# tarjeta-v7.net
KiCad netlist of a schematic drawn in EAGLE
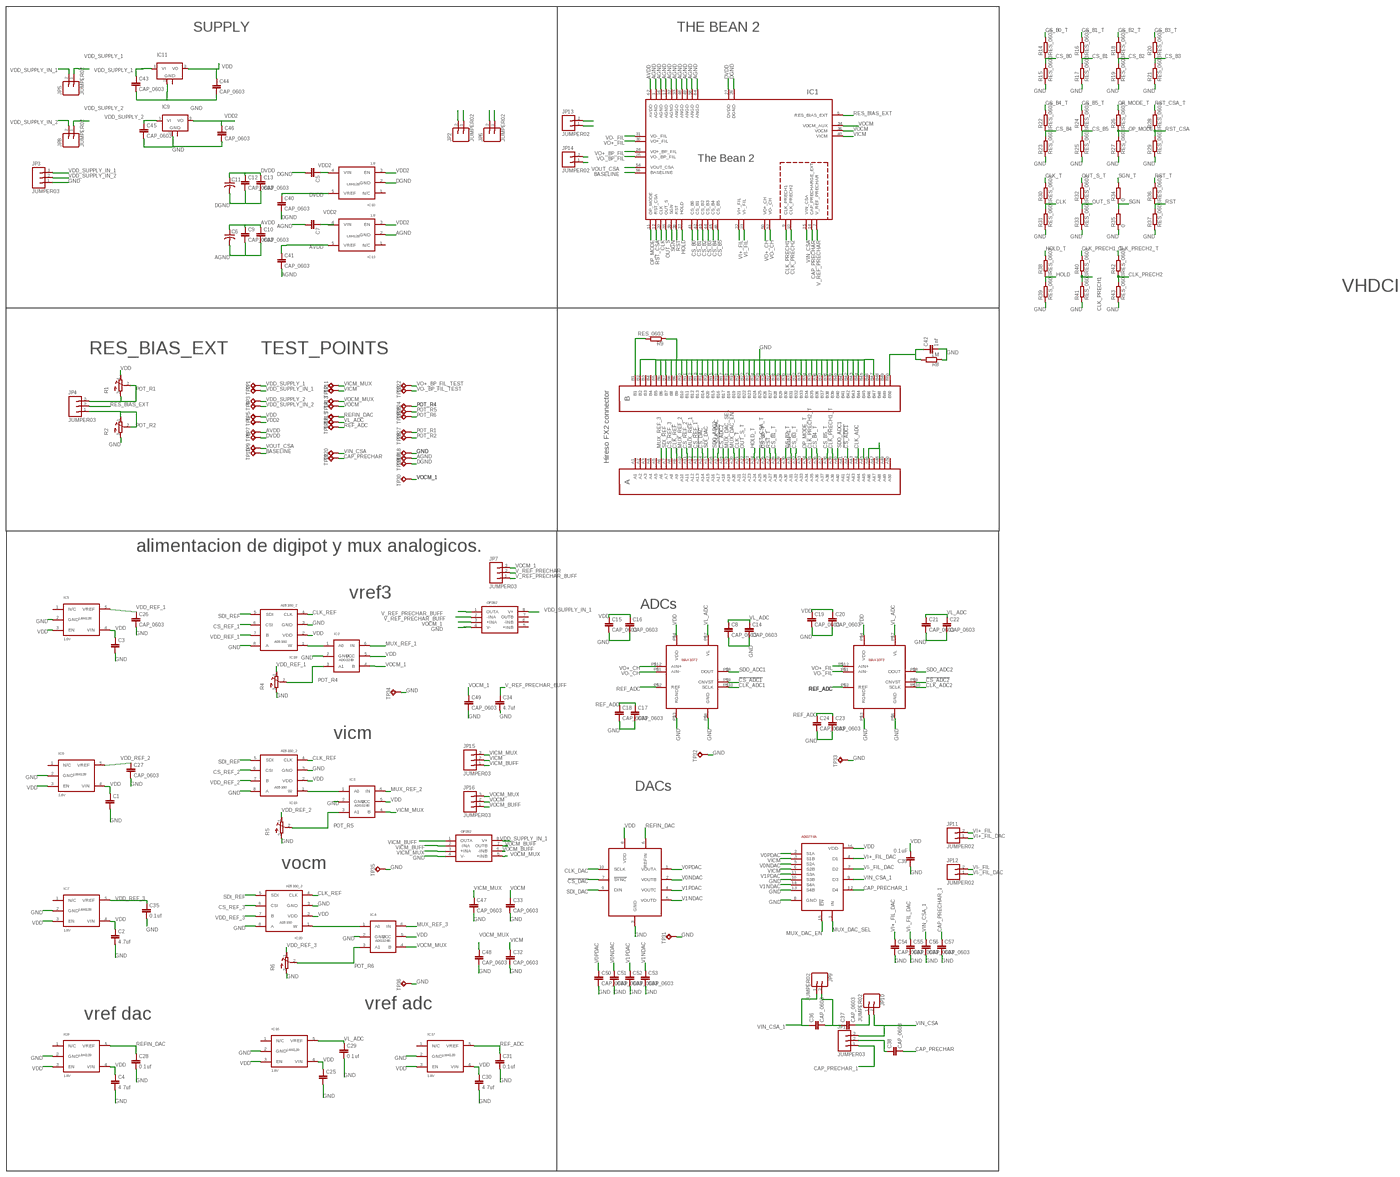
[diagram p0: schematic, sheet 1, overview]
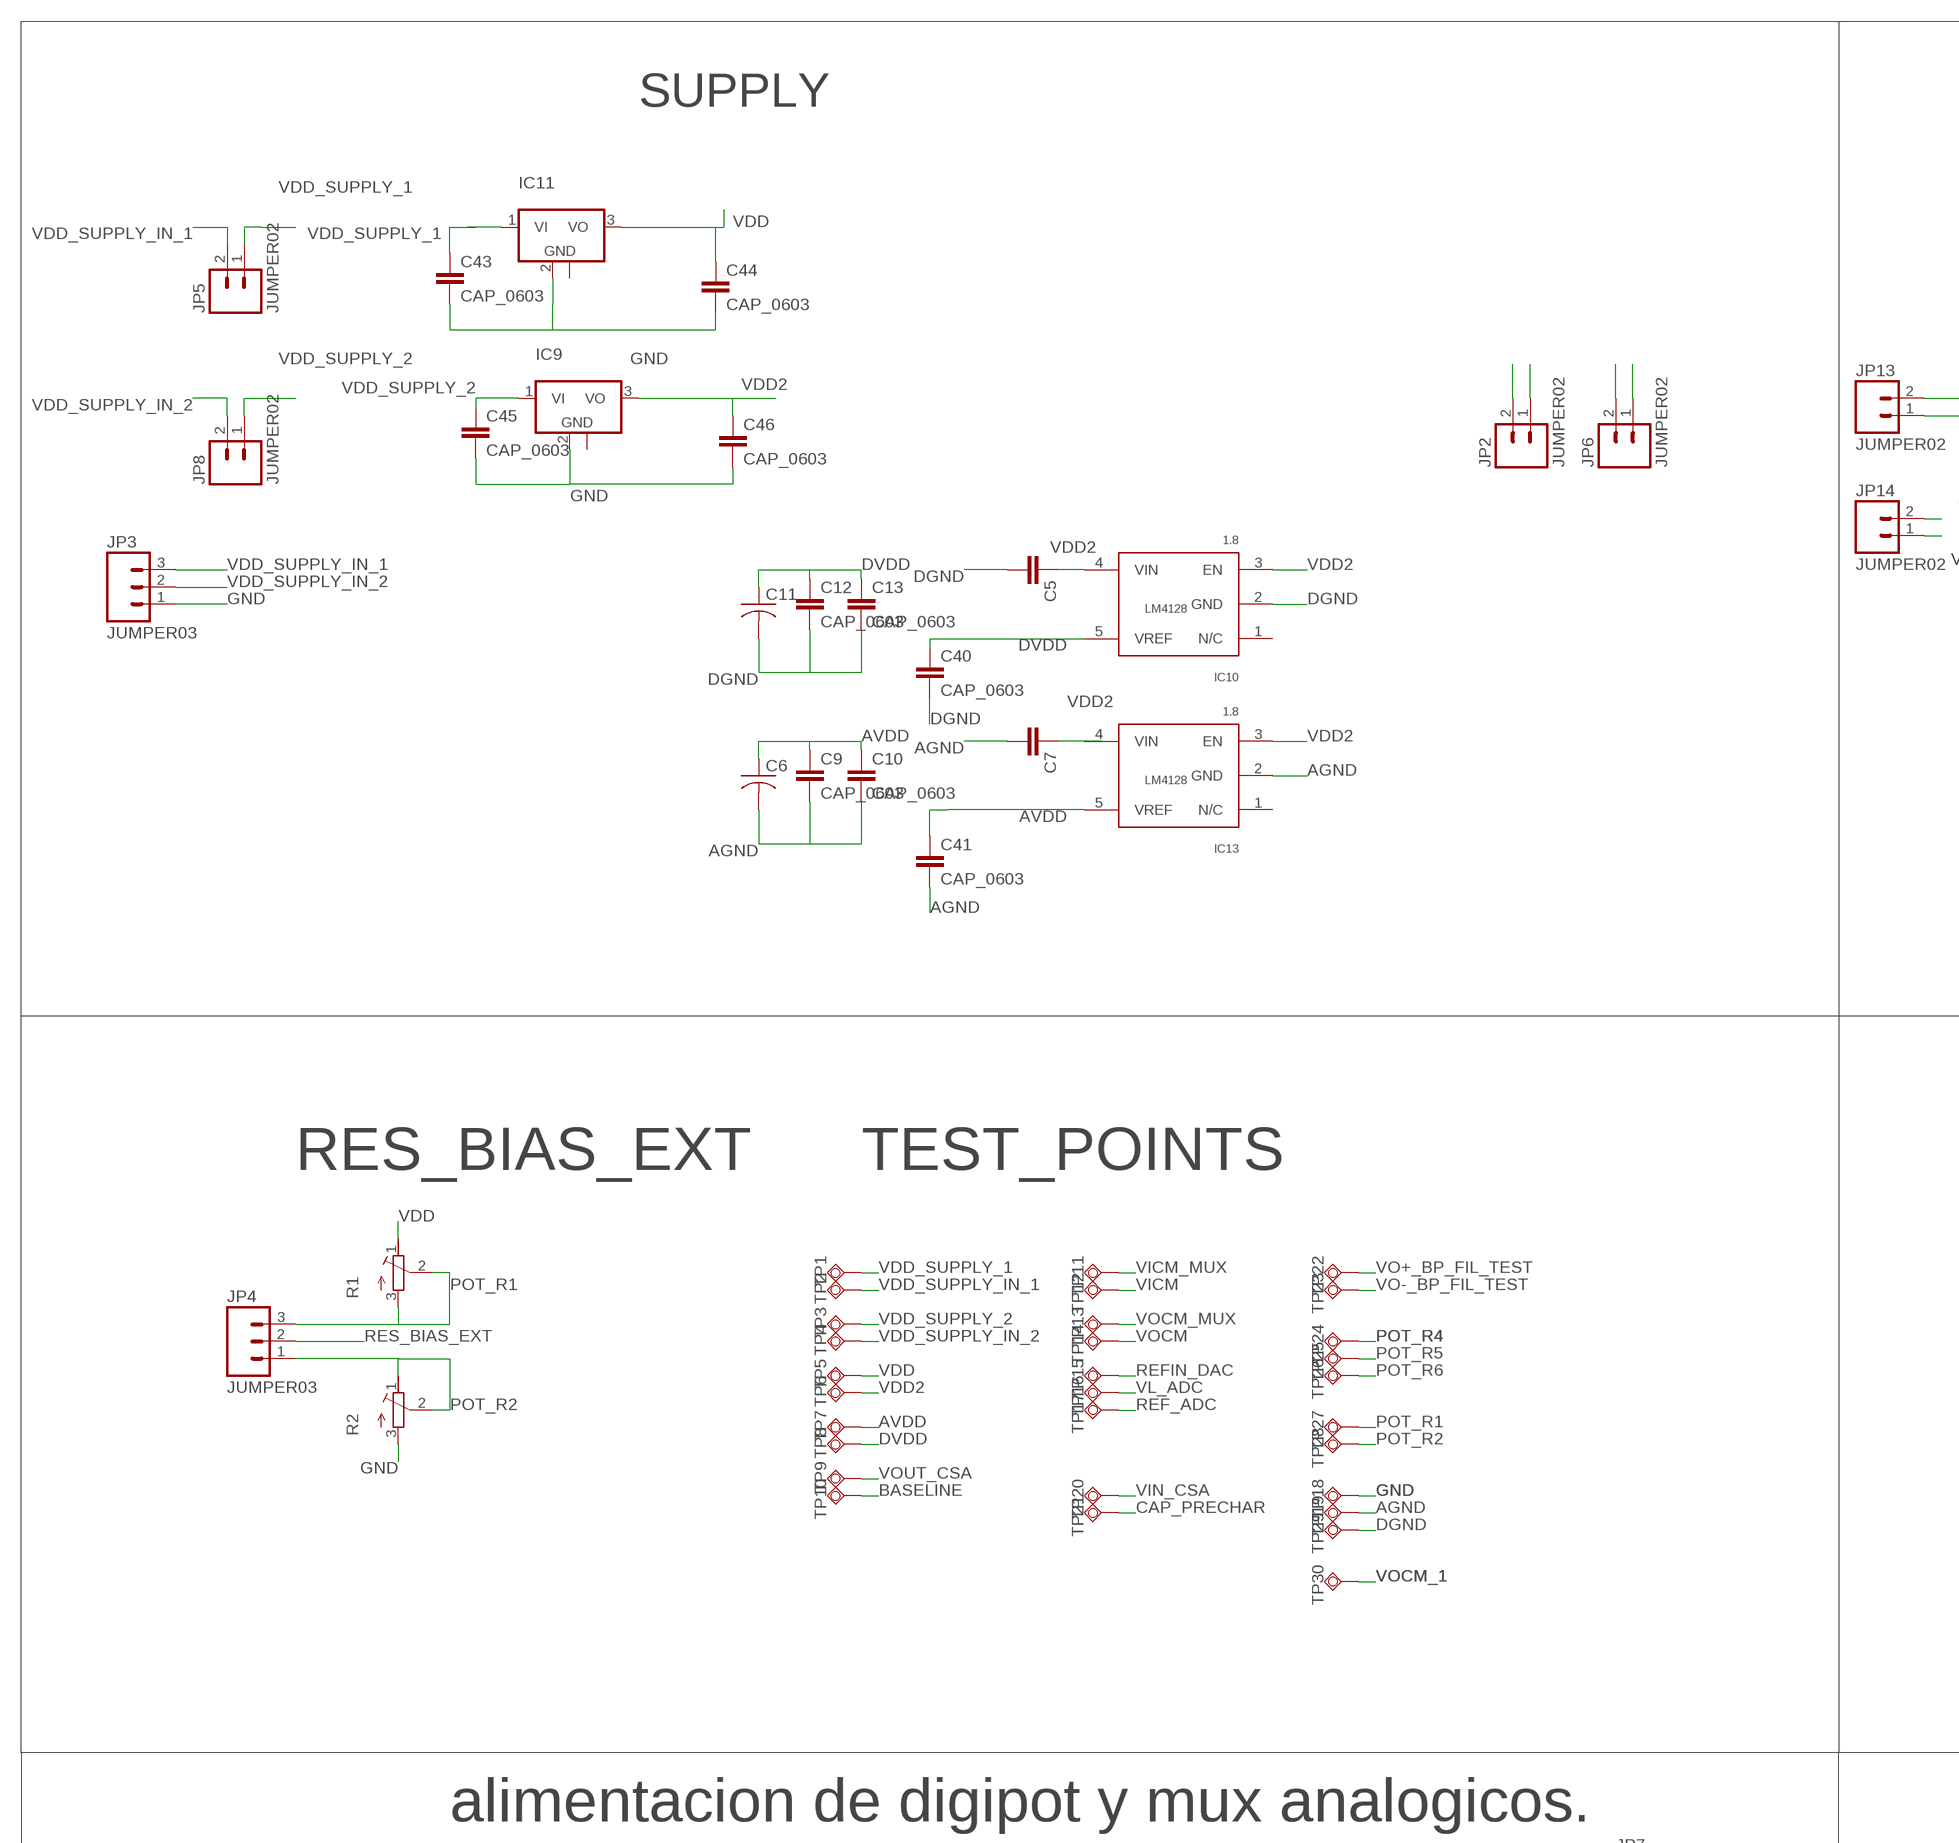
[diagram p1: schematic, sheet 1, part 1 of 4]
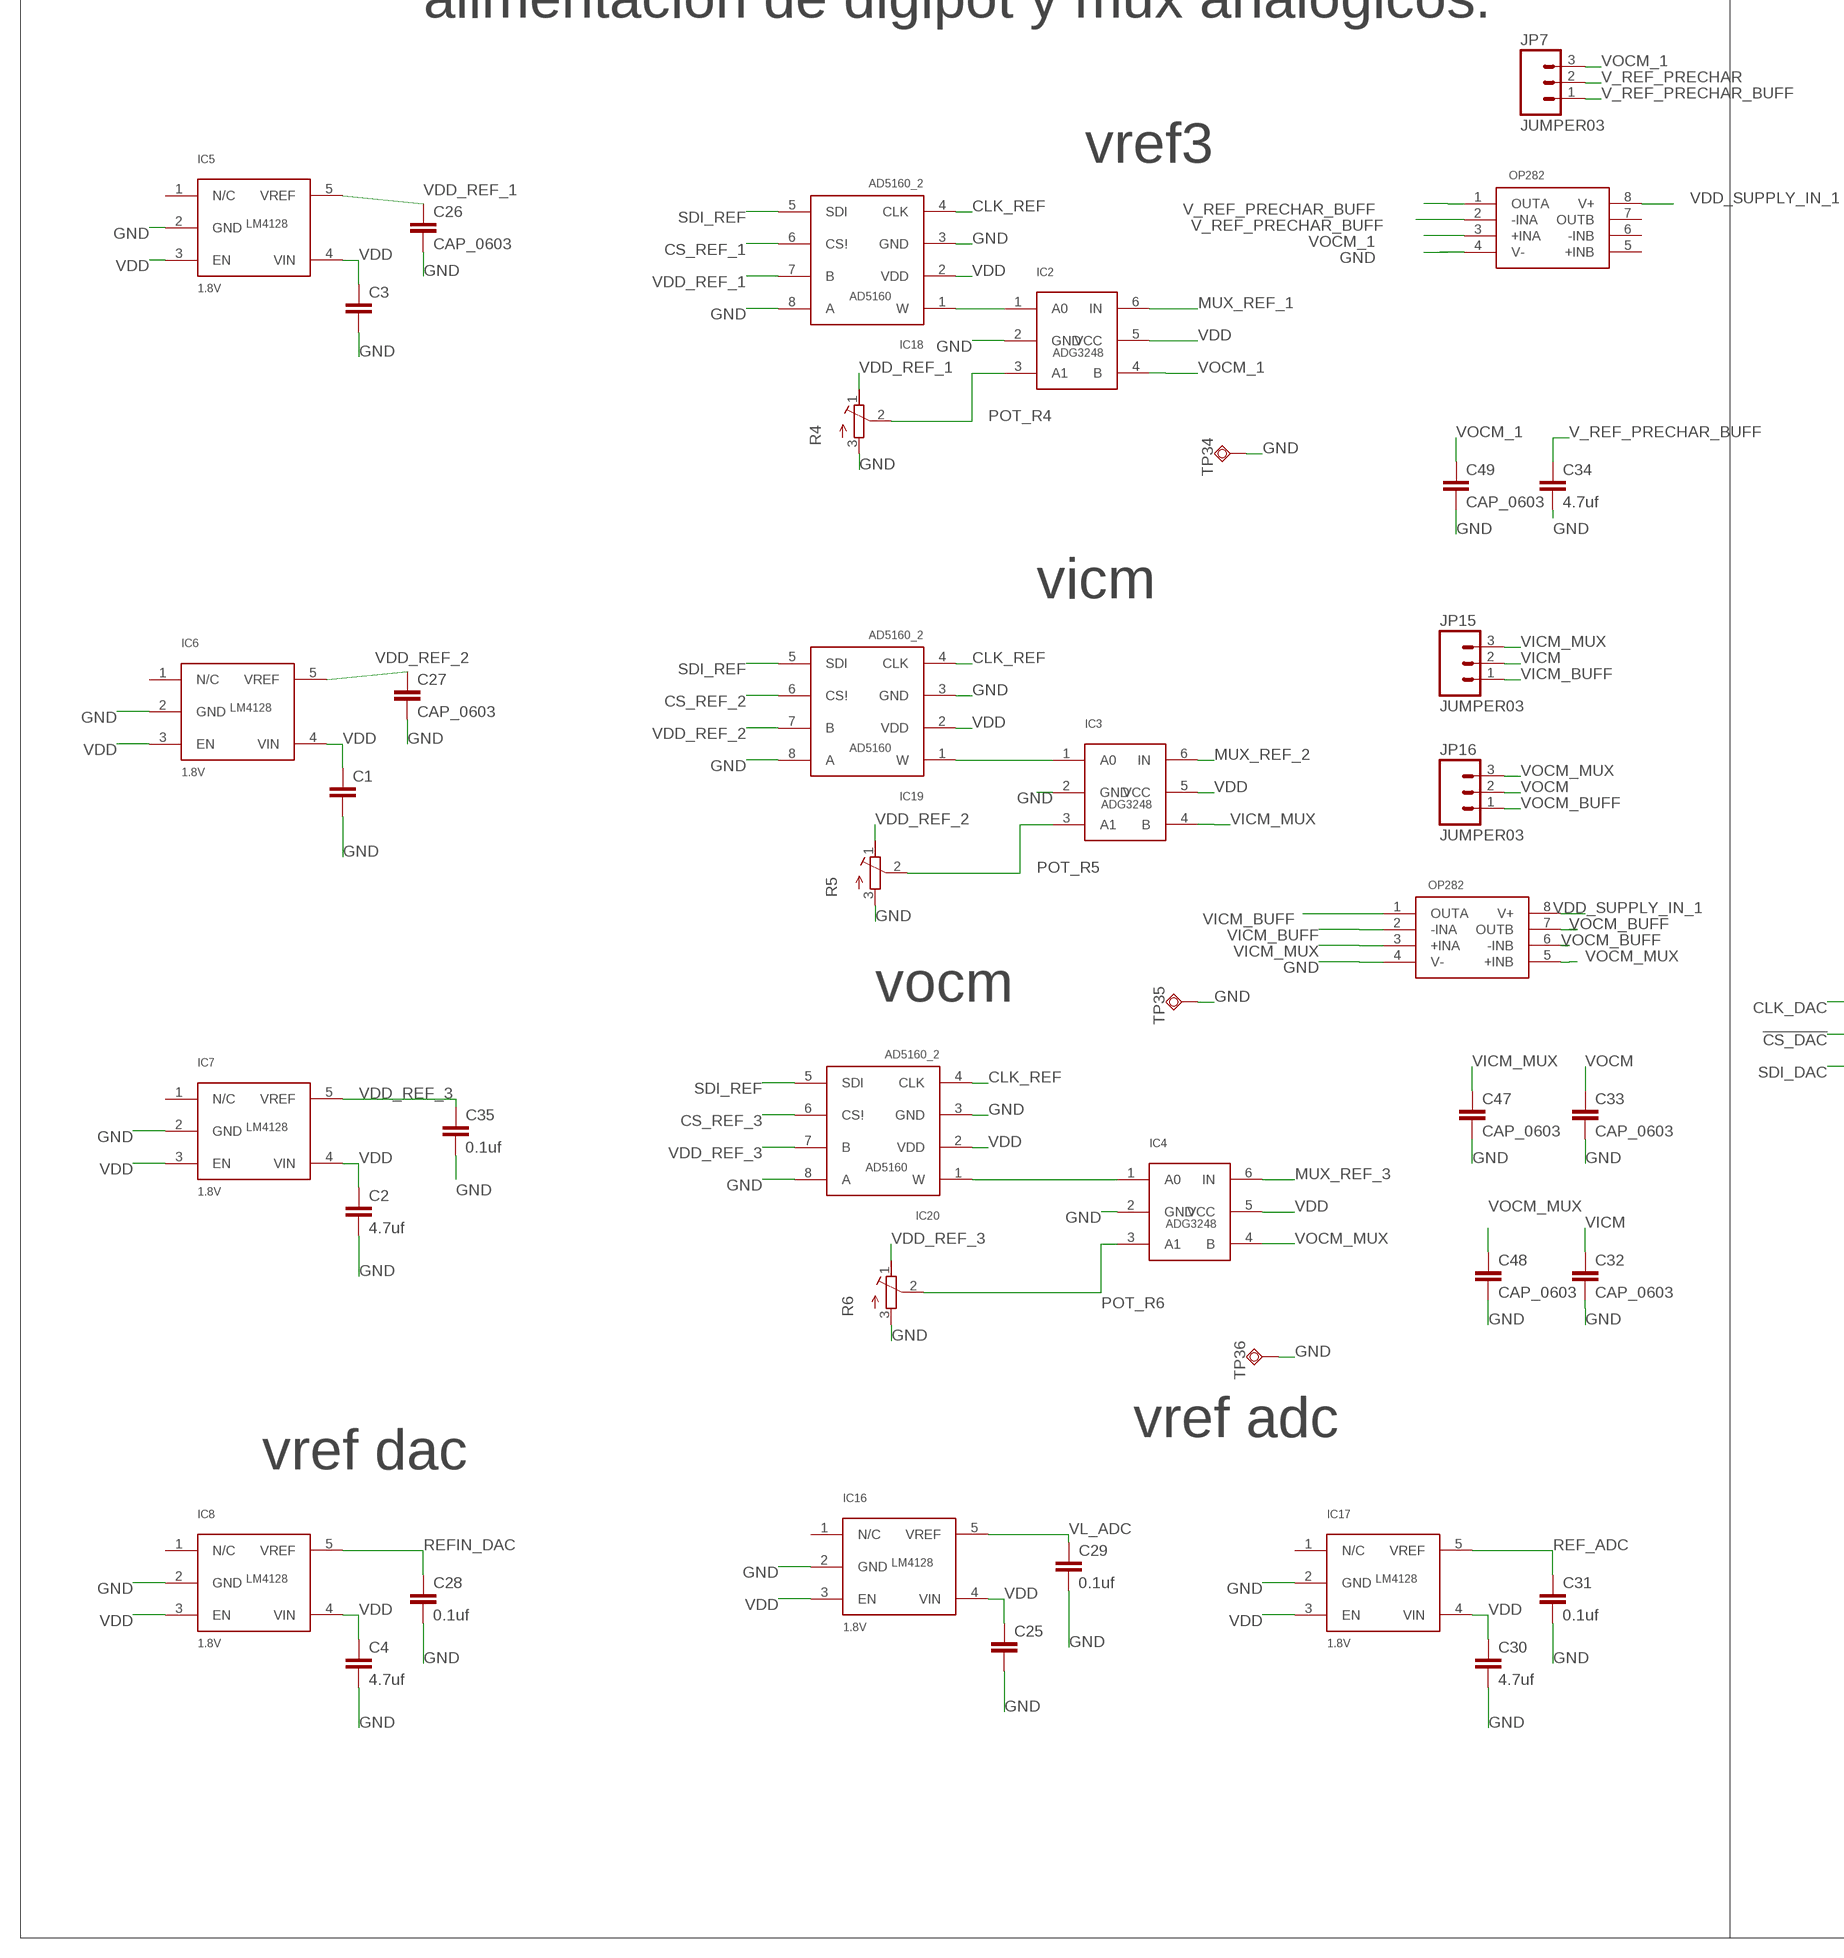
[diagram p2: schematic, sheet 1, part 2 of 4]
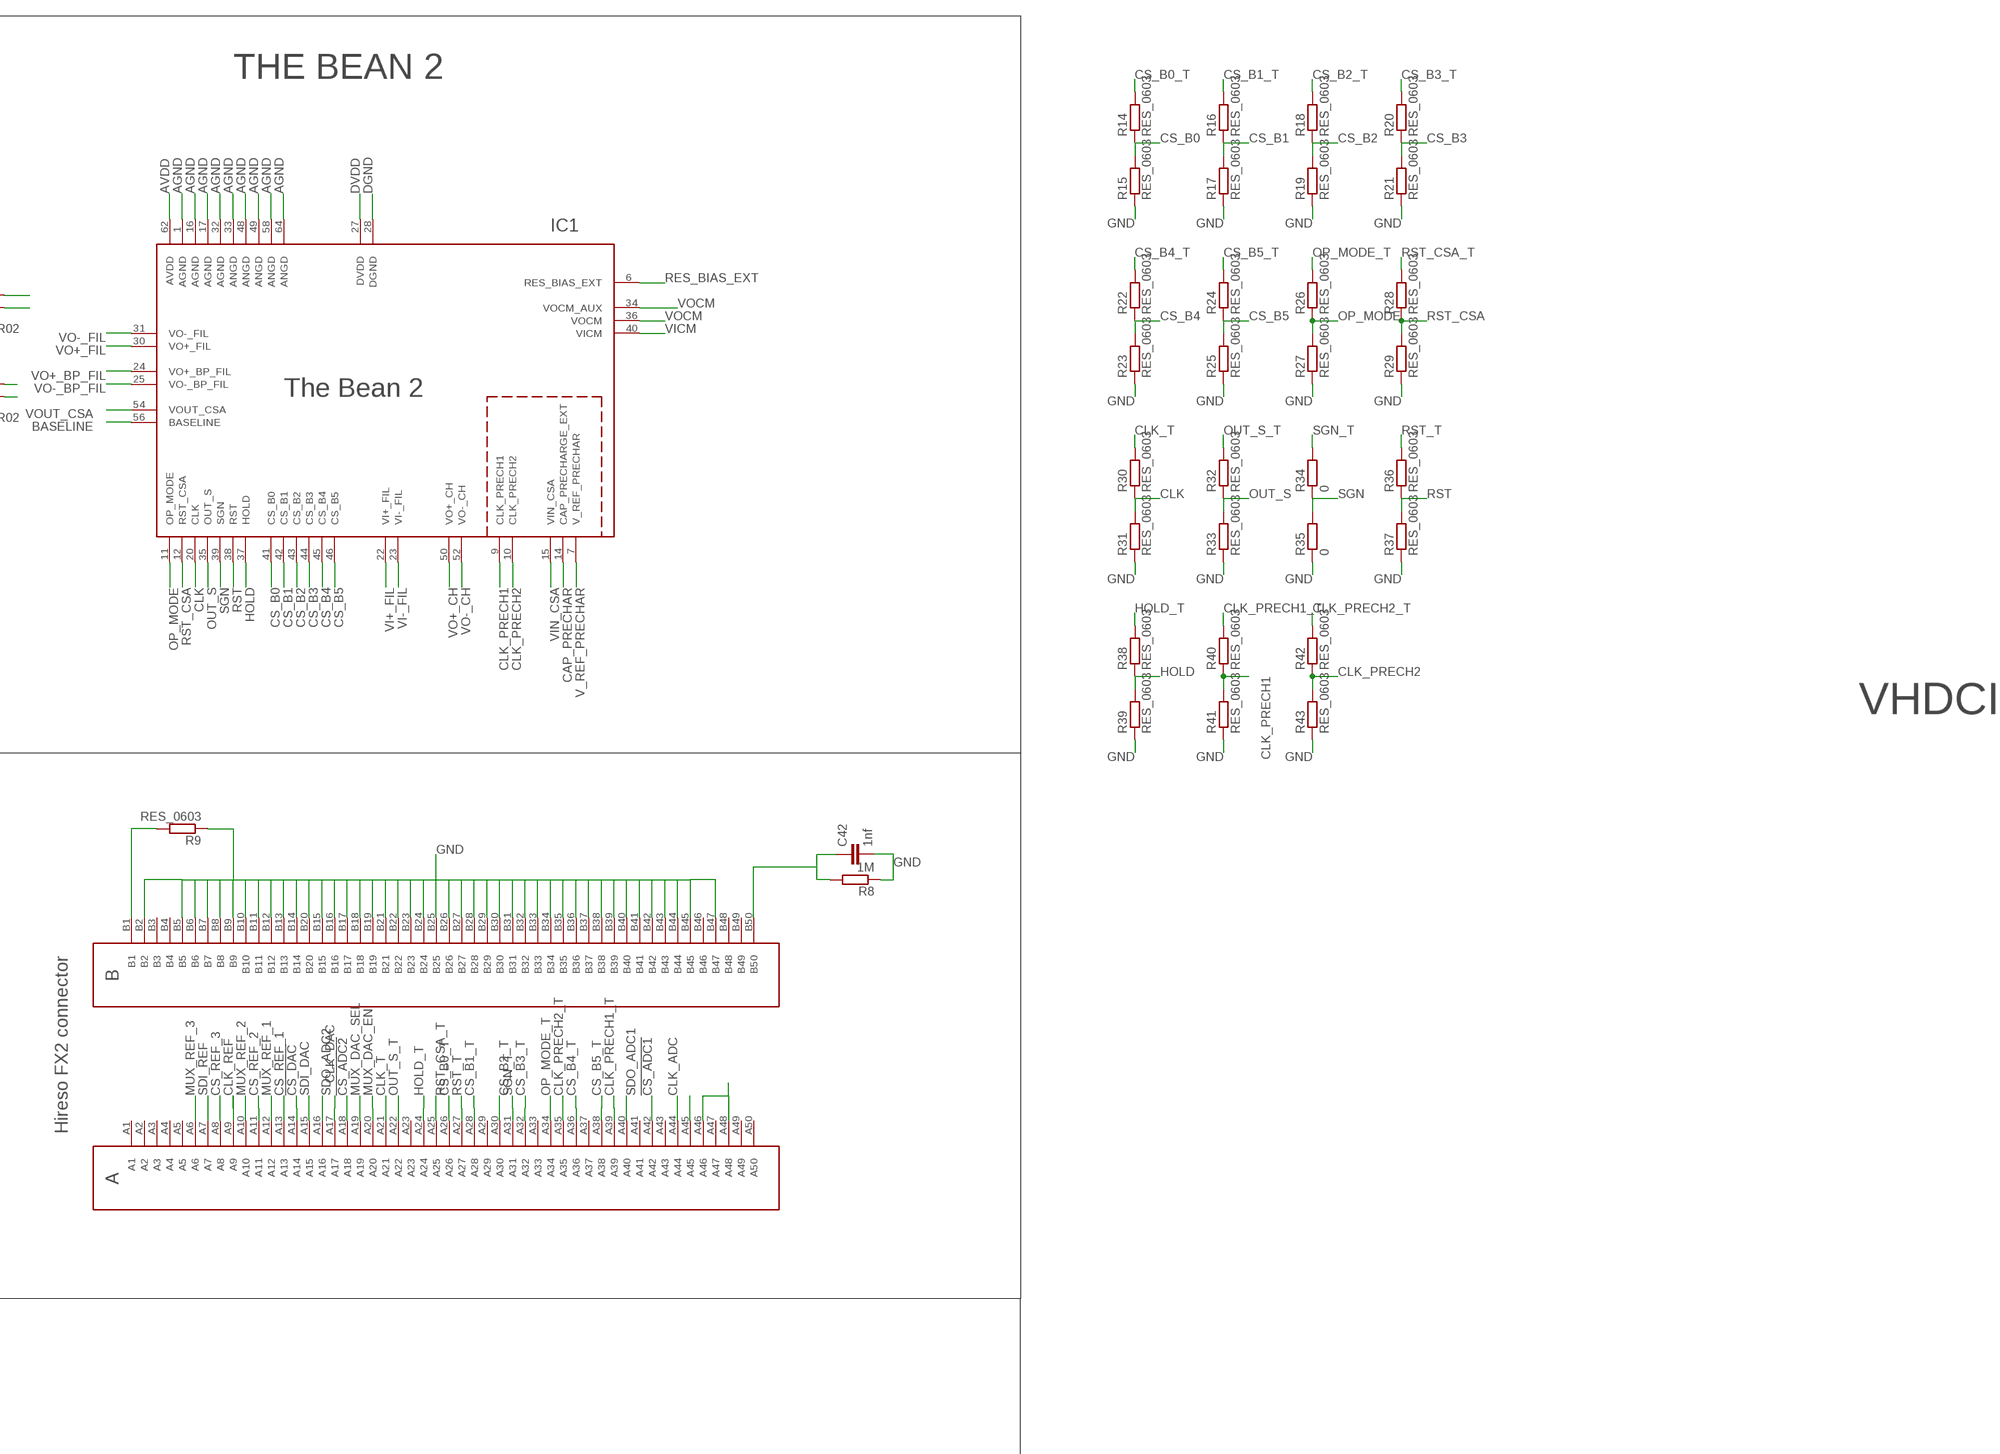
[diagram p3: schematic, sheet 1, part 3 of 4]
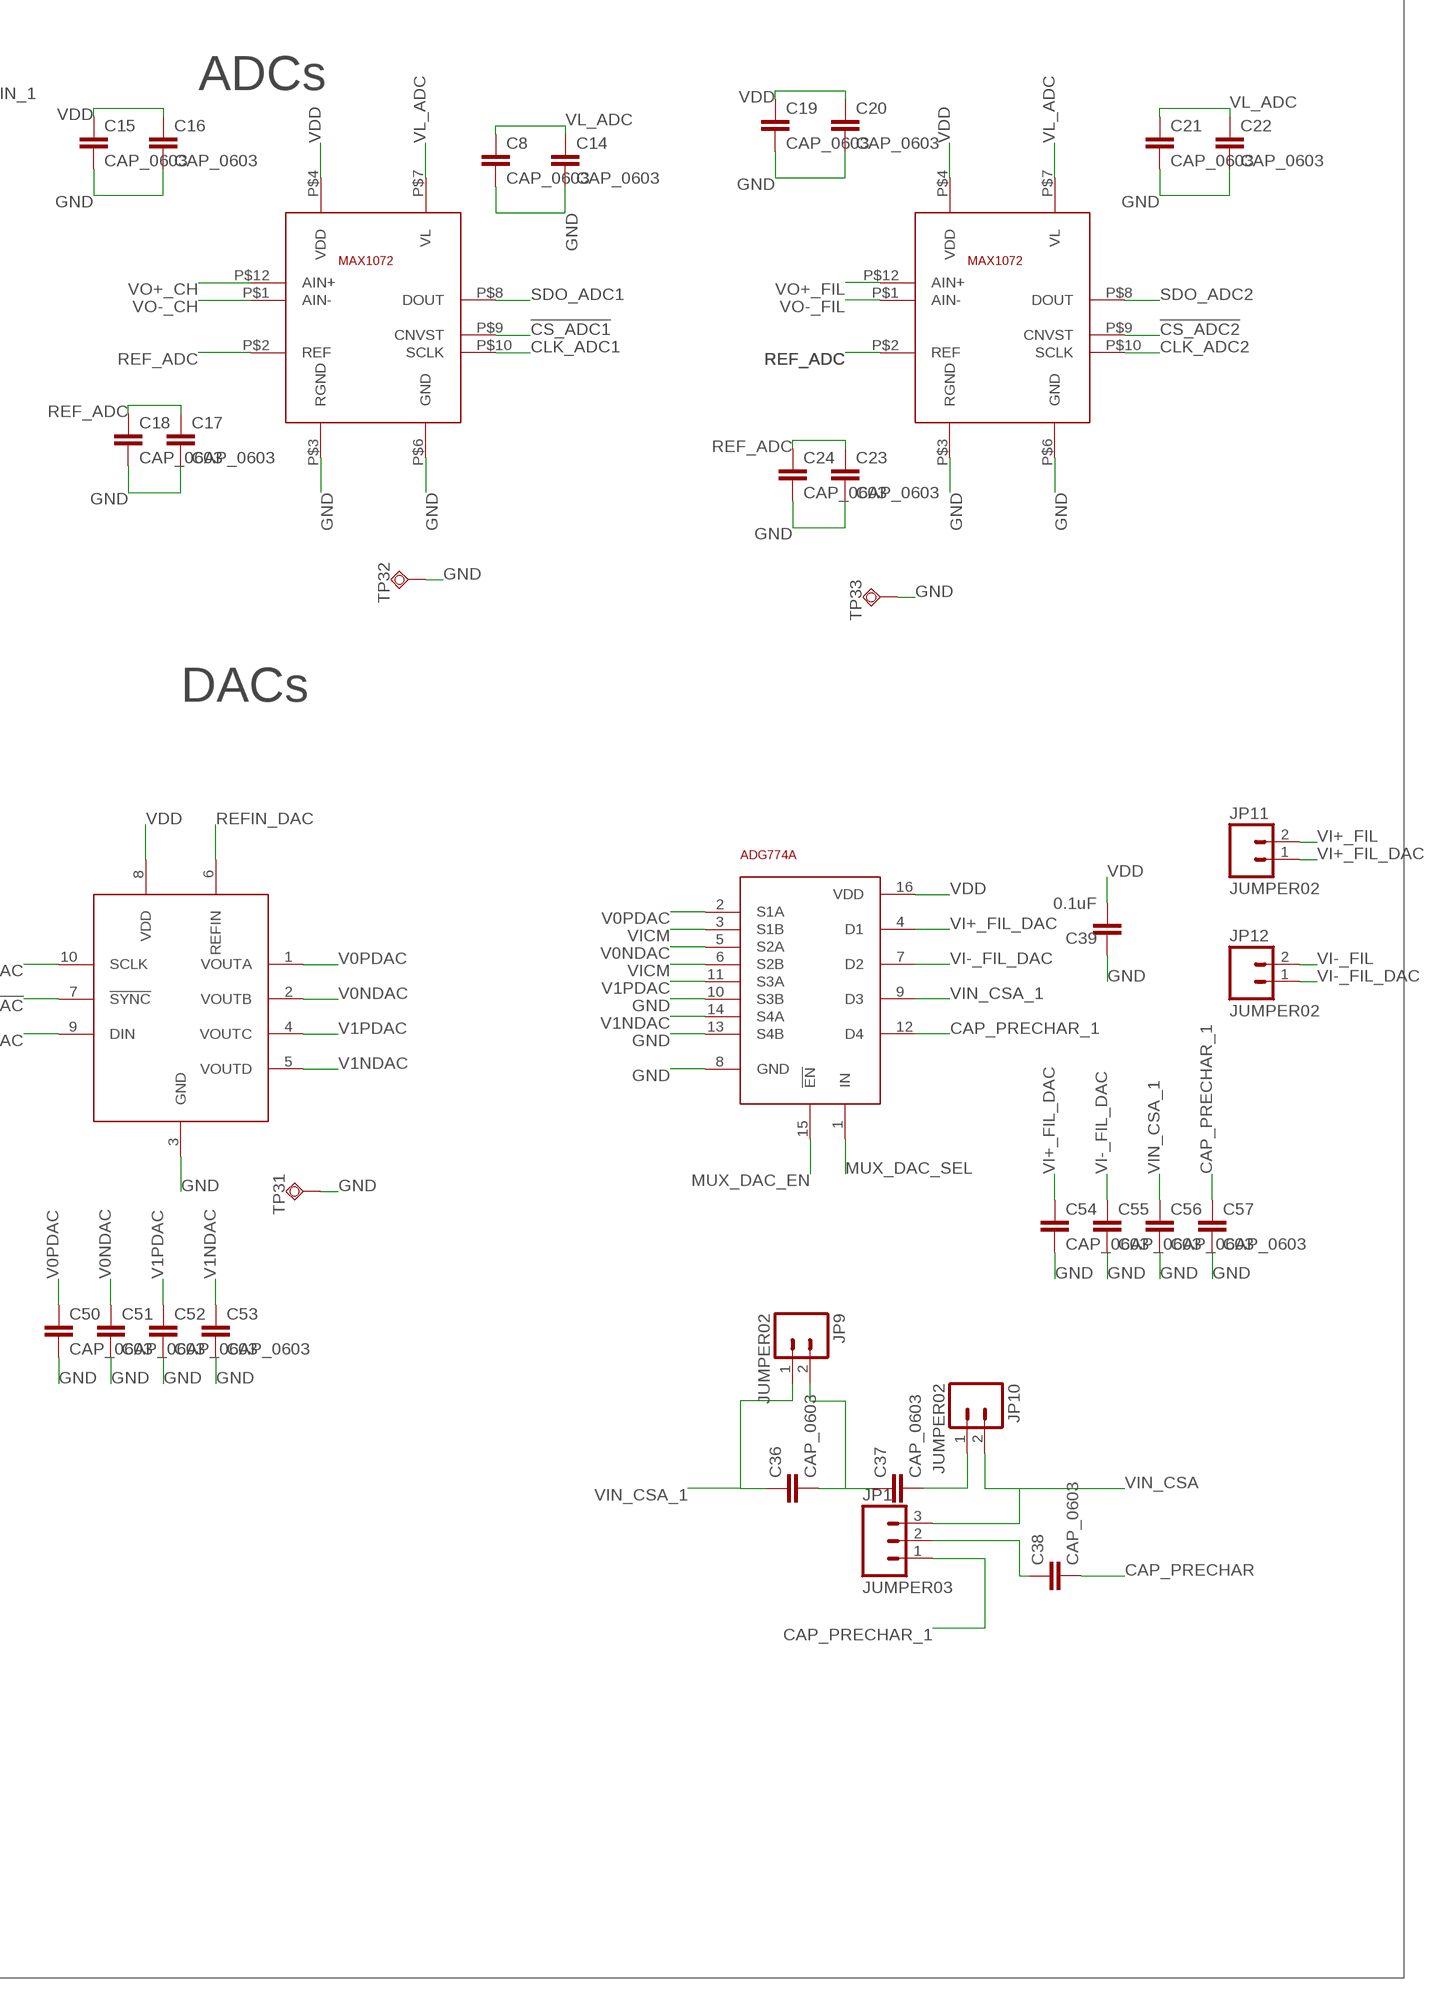
[diagram p4: schematic, sheet 1, part 4 of 4]

(export (version "E")
  (design (tool "Eeschema 10.0.6"))
  (components
    (comp (ref "C1")
      (value "CAP_0402")
      (footprint "eagle-import:C0402")
      (libsource (lib "eagle-import") (part "CAP_0402"))
    )
    (comp (ref "C2")
      (value "4.7uf")
      (footprint "eagle-import:C0402")
      (libsource (lib "eagle-import") (part "CAP_0402"))
    )
    (comp (ref "C3")
      (value "CAP_0402")
      (footprint "eagle-import:C0402")
      (libsource (lib "eagle-import") (part "CAP_0402"))
    )
    (comp (ref "C4")
      (value "4.7uf")
      (footprint "eagle-import:C0402")
      (libsource (lib "eagle-import") (part "CAP_0402"))
    )
    (comp (ref "C5")
      (value "CAP_0402")
      (footprint "eagle-import:C0402")
      (libsource (lib "eagle-import") (part "CAP_0402"))
    )
    (comp (ref "C6")
      (value "CAP_0805")
      (footprint "eagle-import:C0805")
      (libsource (lib "eagle-import") (part "CAP_0805"))
    )
    (comp (ref "C7")
      (value "CAP_0402")
      (footprint "eagle-import:C0402")
      (libsource (lib "eagle-import") (part "CAP_0402"))
    )
    (comp (ref "C8")
      (value "CAP_0603")
      (footprint "eagle-import:C0603")
      (libsource (lib "eagle-import") (part "CAP_0603"))
    )
    (comp (ref "C9")
      (value "CAP_0603")
      (footprint "eagle-import:C0603")
      (libsource (lib "eagle-import") (part "CAP_0603"))
    )
    (comp (ref "C10")
      (value "CAP_0603")
      (footprint "eagle-import:C0603")
      (libsource (lib "eagle-import") (part "CAP_0603"))
    )
    (comp (ref "C11")
      (value "CAP_0805")
      (footprint "eagle-import:C0805")
      (libsource (lib "eagle-import") (part "CAP_0805"))
    )
    (comp (ref "C12")
      (value "CAP_0603")
      (footprint "eagle-import:C0603")
      (libsource (lib "eagle-import") (part "CAP_0603"))
    )
    (comp (ref "C13")
      (value "CAP_0603")
      (footprint "eagle-import:C0603")
      (libsource (lib "eagle-import") (part "CAP_0603"))
    )
    (comp (ref "C14")
      (value "CAP_0603")
      (footprint "eagle-import:C0603")
      (libsource (lib "eagle-import") (part "CAP_0603"))
    )
    (comp (ref "C15")
      (value "CAP_0603")
      (footprint "eagle-import:C0603")
      (libsource (lib "eagle-import") (part "CAP_0603"))
    )
    (comp (ref "C16")
      (value "CAP_0603")
      (footprint "eagle-import:C0603")
      (libsource (lib "eagle-import") (part "CAP_0603"))
    )
    (comp (ref "C17")
      (value "CAP_0603")
      (footprint "eagle-import:C0603")
      (libsource (lib "eagle-import") (part "CAP_0603"))
    )
    (comp (ref "C18")
      (value "CAP_0603")
      (footprint "eagle-import:C0603")
      (libsource (lib "eagle-import") (part "CAP_0603"))
    )
    (comp (ref "C19")
      (value "CAP_0603")
      (footprint "eagle-import:C0603")
      (libsource (lib "eagle-import") (part "CAP_0603"))
    )
    (comp (ref "C20")
      (value "CAP_0603")
      (footprint "eagle-import:C0603")
      (libsource (lib "eagle-import") (part "CAP_0603"))
    )
    (comp (ref "C21")
      (value "CAP_0603")
      (footprint "eagle-import:C0603")
      (libsource (lib "eagle-import") (part "CAP_0603"))
    )
    (comp (ref "C22")
      (value "CAP_0603")
      (footprint "eagle-import:C0603")
      (libsource (lib "eagle-import") (part "CAP_0603"))
    )
    (comp (ref "C23")
      (value "CAP_0603")
      (footprint "eagle-import:C0603")
      (libsource (lib "eagle-import") (part "CAP_0603"))
    )
    (comp (ref "C24")
      (value "CAP_0603")
      (footprint "eagle-import:C0603")
      (libsource (lib "eagle-import") (part "CAP_0603"))
    )
    (comp (ref "C25")
      (value "CAP_0402")
      (footprint "eagle-import:C0402")
      (libsource (lib "eagle-import") (part "CAP_0402"))
    )
    (comp (ref "C26")
      (value "CAP_0603")
      (footprint "eagle-import:C0603")
      (libsource (lib "eagle-import") (part "CAP_0603"))
    )
    (comp (ref "C27")
      (value "CAP_0603")
      (footprint "eagle-import:C0603")
      (libsource (lib "eagle-import") (part "CAP_0603"))
    )
    (comp (ref "C28")
      (value "0.1uf")
      (footprint "eagle-import:C0603")
      (libsource (lib "eagle-import") (part "CAP_0603"))
    )
    (comp (ref "C29")
      (value "0.1uf")
      (footprint "eagle-import:C0603")
      (libsource (lib "eagle-import") (part "CAP_0603"))
    )
    (comp (ref "C30")
      (value "4.7uf")
      (footprint "eagle-import:C0402")
      (libsource (lib "eagle-import") (part "CAP_0402"))
    )
    (comp (ref "C31")
      (value "0.1uf")
      (footprint "eagle-import:C0603")
      (libsource (lib "eagle-import") (part "CAP_0603"))
    )
    (comp (ref "C32")
      (value "CAP_0603")
      (footprint "eagle-import:C0603")
      (libsource (lib "eagle-import") (part "CAP_0603"))
    )
    (comp (ref "C33")
      (value "CAP_0603")
      (footprint "eagle-import:C0603")
      (libsource (lib "eagle-import") (part "CAP_0603"))
    )
    (comp (ref "C34")
      (value "4.7uf")
      (footprint "eagle-import:C0603")
      (libsource (lib "eagle-import") (part "CAP_0603"))
    )
    (comp (ref "C35")
      (value "0.1uf")
      (footprint "eagle-import:C0603")
      (libsource (lib "eagle-import") (part "CAP_0603"))
    )
    (comp (ref "C36")
      (value "CAP_0603")
      (footprint "eagle-import:C0603")
      (libsource (lib "eagle-import") (part "CAP_0603"))
    )
    (comp (ref "C37")
      (value "CAP_0603")
      (footprint "eagle-import:C0603")
      (libsource (lib "eagle-import") (part "CAP_0603"))
    )
    (comp (ref "C38")
      (value "CAP_0603")
      (footprint "eagle-import:C0603")
      (libsource (lib "eagle-import") (part "CAP_0603"))
    )
    (comp (ref "C39")
      (value "0.1uF")
      (footprint "eagle-import:C0603")
      (libsource (lib "eagle-import") (part "CAP_0603"))
    )
    (comp (ref "C40")
      (value "CAP_0603")
      (footprint "eagle-import:C0603")
      (libsource (lib "eagle-import") (part "CAP_0603"))
    )
    (comp (ref "C41")
      (value "CAP_0603")
      (footprint "eagle-import:C0603")
      (libsource (lib "eagle-import") (part "CAP_0603"))
    )
    (comp (ref "C42")
      (value "1nf")
      (footprint "eagle-import:C0603")
      (libsource (lib "eagle-import") (part "CAP_0603"))
    )
    (comp (ref "C43")
      (value "CAP_0603")
      (footprint "eagle-import:C0603")
      (libsource (lib "eagle-import") (part "CAP_0603"))
    )
    (comp (ref "C44")
      (value "CAP_0603")
      (footprint "eagle-import:C0603")
      (libsource (lib "eagle-import") (part "CAP_0603"))
    )
    (comp (ref "C45")
      (value "CAP_0603")
      (footprint "eagle-import:C0603")
      (libsource (lib "eagle-import") (part "CAP_0603"))
    )
    (comp (ref "C46")
      (value "CAP_0603")
      (footprint "eagle-import:C0603")
      (libsource (lib "eagle-import") (part "CAP_0603"))
    )
    (comp (ref "C47")
      (value "CAP_0603")
      (footprint "eagle-import:C0603")
      (libsource (lib "eagle-import") (part "CAP_0603"))
    )
    (comp (ref "C48")
      (value "CAP_0603")
      (footprint "eagle-import:C0603")
      (libsource (lib "eagle-import") (part "CAP_0603"))
    )
    (comp (ref "C49")
      (value "CAP_0603")
      (footprint "eagle-import:C0603")
      (libsource (lib "eagle-import") (part "CAP_0603"))
    )
    (comp (ref "C50")
      (value "CAP_0603")
      (footprint "eagle-import:C0603")
      (libsource (lib "eagle-import") (part "CAP_0603"))
    )
    (comp (ref "C51")
      (value "CAP_0603")
      (footprint "eagle-import:C0603")
      (libsource (lib "eagle-import") (part "CAP_0603"))
    )
    (comp (ref "C52")
      (value "CAP_0603")
      (footprint "eagle-import:C0603")
      (libsource (lib "eagle-import") (part "CAP_0603"))
    )
    (comp (ref "C53")
      (value "CAP_0603")
      (footprint "eagle-import:C0603")
      (libsource (lib "eagle-import") (part "CAP_0603"))
    )
    (comp (ref "C54")
      (value "CAP_0603")
      (footprint "eagle-import:C0603")
      (libsource (lib "eagle-import") (part "CAP_0603"))
    )
    (comp (ref "C55")
      (value "CAP_0603")
      (footprint "eagle-import:C0603")
      (libsource (lib "eagle-import") (part "CAP_0603"))
    )
    (comp (ref "C56")
      (value "CAP_0603")
      (footprint "eagle-import:C0603")
      (libsource (lib "eagle-import") (part "CAP_0603"))
    )
    (comp (ref "C57")
      (value "CAP_0603")
      (footprint "eagle-import:C0603")
      (libsource (lib "eagle-import") (part "CAP_0603"))
    )
    (comp (ref "IC1")
      (value "THE_BEAN_2")
      (footprint "eagle-import:QFN64")
      (libsource (lib "eagle-import") (part "THE_BEAN_2"))
    )
    (comp (ref "IC2")
      (value "ADG3248")
      (footprint "eagle-import:SC70")
      (libsource (lib "eagle-import") (part "ADG3248"))
    )
    (comp (ref "IC3")
      (value "ADG3248")
      (footprint "eagle-import:SC70")
      (libsource (lib "eagle-import") (part "ADG3248"))
    )
    (comp (ref "IC4")
      (value "ADG3248")
      (footprint "eagle-import:SC70")
      (libsource (lib "eagle-import") (part "ADG3248"))
    )
    (comp (ref "IC5")
      (value "1.8V")
      (footprint "eagle-import:SOT23-5L_2")
      (libsource (lib "eagle-import") (part "LM4128_2"))
    )
    (comp (ref "IC6")
      (value "1.8V")
      (footprint "eagle-import:SOT23-5L_2")
      (libsource (lib "eagle-import") (part "LM4128_2"))
    )
    (comp (ref "IC7")
      (value "1.8V")
      (footprint "eagle-import:SOT23-5L_2")
      (libsource (lib "eagle-import") (part "LM4128_2"))
    )
    (comp (ref "IC8")
      (value "1.8V")
      (footprint "eagle-import:SOT23-5L_2")
      (libsource (lib "eagle-import") (part "LM4128_2"))
    )
    (comp (ref "IC9")
      (value "UA78M33DCY")
      (footprint "eagle-import:SOT223")
      (libsource (lib "eagle-import") (part "UA78MDCY33"))
    )
    (comp (ref "IC10")
      (value "1.8")
      (footprint "eagle-import:SOT23-5L_2")
      (libsource (lib "eagle-import") (part "LM4128_2"))
    )
    (comp (ref "IC11")
      (value "UA78M33DCY")
      (footprint "eagle-import:SOT223")
      (libsource (lib "eagle-import") (part "UA78MDCY33"))
    )
    (comp (ref "IC12")
      (value "OP282")
      (footprint "eagle-import:MSOP8")
      (libsource (lib "eagle-import") (part "OP282"))
    )
    (comp (ref "IC13")
      (value "1.8")
      (footprint "eagle-import:SOT23-5L_2")
      (libsource (lib "eagle-import") (part "LM4128_2"))
    )
    (comp (ref "IC14")
      (value "OP282")
      (footprint "eagle-import:MSOP8")
      (libsource (lib "eagle-import") (part "OP282"))
    )
    (comp (ref "IC16")
      (value "1.8V")
      (footprint "eagle-import:SOT23-5L_2")
      (libsource (lib "eagle-import") (part "LM4128_2"))
    )
    (comp (ref "IC17")
      (value "1.8V")
      (footprint "eagle-import:SOT23-5L_2")
      (libsource (lib "eagle-import") (part "LM4128_2"))
    )
    (comp (ref "IC18")
      (value "AD5160_2")
      (footprint "eagle-import:SOT23-8_2")
      (libsource (lib "eagle-import") (part "AD5160_2"))
    )
    (comp (ref "IC19")
      (value "AD5160_2")
      (footprint "eagle-import:SOT23-8_2")
      (libsource (lib "eagle-import") (part "AD5160_2"))
    )
    (comp (ref "IC20")
      (value "AD5160_2")
      (footprint "eagle-import:SOT23-8_2")
      (libsource (lib "eagle-import") (part "AD5160_2"))
    )
    (comp (ref "IC21")
      (value "ADG774A")
      (footprint "eagle-import:QSOP16")
      (libsource (lib "eagle-import") (part "ADG774A"))
    )
    (comp (ref "IC22")
      (value "MAX1072")
      (footprint "eagle-import:TQFN12")
      (libsource (lib "eagle-import") (part "MAX1072"))
    )
    (comp (ref "IC23")
      (value "DAC7554")
      (footprint "eagle-import:MSOP10")
      (libsource (lib "eagle-import") (part "DAC7554"))
    )
    (comp (ref "J1")
      (value "HIRESO_FX_CONNECTOR")
      (footprint "eagle-import:FX2-100S-1.27")
      (libsource (lib "eagle-import") (part "HIRESO_FX_CONNECTOR"))
    )
    (comp (ref "JP1")
      (value "JUMPER03")
      (footprint "eagle-import:1X03")
      (libsource (lib "eagle-import") (part "JUMPER03"))
    )
    (comp (ref "JP2")
      (value "JUMPER02")
      (footprint "eagle-import:1X02")
      (libsource (lib "eagle-import") (part "JUMPER02"))
    )
    (comp (ref "JP3")
      (value "JUMPER03")
      (footprint "eagle-import:1X03")
      (libsource (lib "eagle-import") (part "JUMPER03"))
    )
    (comp (ref "JP4")
      (value "JUMPER03")
      (footprint "eagle-import:1X03")
      (libsource (lib "eagle-import") (part "JUMPER03"))
    )
    (comp (ref "JP5")
      (value "JUMPER02")
      (footprint "eagle-import:1X02")
      (libsource (lib "eagle-import") (part "JUMPER02"))
    )
    (comp (ref "JP6")
      (value "JUMPER02")
      (footprint "eagle-import:1X02")
      (libsource (lib "eagle-import") (part "JUMPER02"))
    )
    (comp (ref "JP7")
      (value "JUMPER03")
      (footprint "eagle-import:1X03")
      (libsource (lib "eagle-import") (part "JUMPER03"))
    )
    (comp (ref "JP8")
      (value "JUMPER02")
      (footprint "eagle-import:1X02")
      (libsource (lib "eagle-import") (part "JUMPER02"))
    )
    (comp (ref "JP9")
      (value "JUMPER02")
      (footprint "eagle-import:1X02")
      (libsource (lib "eagle-import") (part "JUMPER02"))
    )
    (comp (ref "JP10")
      (value "JUMPER02")
      (footprint "eagle-import:1X02")
      (libsource (lib "eagle-import") (part "JUMPER02"))
    )
    (comp (ref "JP11")
      (value "JUMPER02")
      (footprint "eagle-import:1X02")
      (libsource (lib "eagle-import") (part "JUMPER02"))
    )
    (comp (ref "JP12")
      (value "JUMPER02")
      (footprint "eagle-import:1X02")
      (libsource (lib "eagle-import") (part "JUMPER02"))
    )
    (comp (ref "JP13")
      (value "JUMPER02")
      (footprint "eagle-import:1X02")
      (libsource (lib "eagle-import") (part "JUMPER02"))
    )
    (comp (ref "JP14")
      (value "JUMPER02")
      (footprint "eagle-import:1X02")
      (libsource (lib "eagle-import") (part "JUMPER02"))
    )
    (comp (ref "JP15")
      (value "JUMPER03")
      (footprint "eagle-import:1X03")
      (libsource (lib "eagle-import") (part "JUMPER03"))
    )
    (comp (ref "JP16")
      (value "JUMPER03")
      (footprint "eagle-import:1X03")
      (libsource (lib "eagle-import") (part "JUMPER03"))
    )
    (comp (ref "R1")
      (value "TRIMMER_ST5")
      (footprint "eagle-import:ST-5EW")
      (libsource (lib "eagle-import") (part "TRIMMER_ST5"))
    )
    (comp (ref "R2")
      (value "TRIMMER_ST5")
      (footprint "eagle-import:ST-5EW")
      (libsource (lib "eagle-import") (part "TRIMMER_ST5"))
    )
    (comp (ref "R4")
      (value "TRIMMER_ST5")
      (footprint "eagle-import:ST-5EW")
      (libsource (lib "eagle-import") (part "TRIMMER_ST5"))
    )
    (comp (ref "R5")
      (value "TRIMMER_ST5")
      (footprint "eagle-import:ST-5EW")
      (libsource (lib "eagle-import") (part "TRIMMER_ST5"))
    )
    (comp (ref "R6")
      (value "TRIMMER_ST5")
      (footprint "eagle-import:ST-5EW")
      (libsource (lib "eagle-import") (part "TRIMMER_ST5"))
    )
    (comp (ref "R8")
      (value "1M")
      (footprint "eagle-import:R0603")
      (libsource (lib "eagle-import") (part "RES_0603"))
    )
    (comp (ref "R9")
      (value "RES_0603")
      (footprint "eagle-import:R0603")
      (libsource (lib "eagle-import") (part "RES_0603"))
    )
    (comp (ref "R14")
      (value "RES_0603")
      (footprint "eagle-import:R0603")
      (libsource (lib "eagle-import") (part "RES_0603"))
    )
    (comp (ref "R15")
      (value "RES_0603")
      (footprint "eagle-import:R0603")
      (libsource (lib "eagle-import") (part "RES_0603"))
    )
    (comp (ref "R16")
      (value "RES_0603")
      (footprint "eagle-import:R0603")
      (libsource (lib "eagle-import") (part "RES_0603"))
    )
    (comp (ref "R17")
      (value "RES_0603")
      (footprint "eagle-import:R0603")
      (libsource (lib "eagle-import") (part "RES_0603"))
    )
    (comp (ref "R18")
      (value "RES_0603")
      (footprint "eagle-import:R0603")
      (libsource (lib "eagle-import") (part "RES_0603"))
    )
    (comp (ref "R19")
      (value "RES_0603")
      (footprint "eagle-import:R0603")
      (libsource (lib "eagle-import") (part "RES_0603"))
    )
    (comp (ref "R20")
      (value "RES_0603")
      (footprint "eagle-import:R0603")
      (libsource (lib "eagle-import") (part "RES_0603"))
    )
    (comp (ref "R21")
      (value "RES_0603")
      (footprint "eagle-import:R0603")
      (libsource (lib "eagle-import") (part "RES_0603"))
    )
    (comp (ref "R22")
      (value "RES_0603")
      (footprint "eagle-import:R0603")
      (libsource (lib "eagle-import") (part "RES_0603"))
    )
    (comp (ref "R23")
      (value "RES_0603")
      (footprint "eagle-import:R0603")
      (libsource (lib "eagle-import") (part "RES_0603"))
    )
    (comp (ref "R24")
      (value "RES_0603")
      (footprint "eagle-import:R0603")
      (libsource (lib "eagle-import") (part "RES_0603"))
    )
    (comp (ref "R25")
      (value "RES_0603")
      (footprint "eagle-import:R0603")
      (libsource (lib "eagle-import") (part "RES_0603"))
    )
    (comp (ref "R26")
      (value "RES_0603")
      (footprint "eagle-import:R0603")
      (libsource (lib "eagle-import") (part "RES_0603"))
    )
    (comp (ref "R27")
      (value "RES_0603")
      (footprint "eagle-import:R0603")
      (libsource (lib "eagle-import") (part "RES_0603"))
    )
    (comp (ref "R28")
      (value "RES_0603")
      (footprint "eagle-import:R0603")
      (libsource (lib "eagle-import") (part "RES_0603"))
    )
    (comp (ref "R29")
      (value "RES_0603")
      (footprint "eagle-import:R0603")
      (libsource (lib "eagle-import") (part "RES_0603"))
    )
    (comp (ref "R30")
      (value "RES_0603")
      (footprint "eagle-import:R0603")
      (libsource (lib "eagle-import") (part "RES_0603"))
    )
    (comp (ref "R31")
      (value "RES_0603")
      (footprint "eagle-import:R0603")
      (libsource (lib "eagle-import") (part "RES_0603"))
    )
    (comp (ref "R32")
      (value "RES_0603")
      (footprint "eagle-import:R0603")
      (libsource (lib "eagle-import") (part "RES_0603"))
    )
    (comp (ref "R33")
      (value "RES_0603")
      (footprint "eagle-import:R0603")
      (libsource (lib "eagle-import") (part "RES_0603"))
    )
    (comp (ref "R34")
      (value "0")
      (footprint "eagle-import:R0603")
      (libsource (lib "eagle-import") (part "RES_0603"))
    )
    (comp (ref "R35")
      (value "0")
      (footprint "eagle-import:R0603")
      (libsource (lib "eagle-import") (part "RES_0603"))
    )
    (comp (ref "R36")
      (value "RES_0603")
      (footprint "eagle-import:R0603")
      (libsource (lib "eagle-import") (part "RES_0603"))
    )
    (comp (ref "R37")
      (value "RES_0603")
      (footprint "eagle-import:R0603")
      (libsource (lib "eagle-import") (part "RES_0603"))
    )
    (comp (ref "R38")
      (value "RES_0603")
      (footprint "eagle-import:R0603")
      (libsource (lib "eagle-import") (part "RES_0603"))
    )
    (comp (ref "R39")
      (value "RES_0603")
      (footprint "eagle-import:R0603")
      (libsource (lib "eagle-import") (part "RES_0603"))
    )
    (comp (ref "R40")
      (value "RES_0603")
      (footprint "eagle-import:R0603")
      (libsource (lib "eagle-import") (part "RES_0603"))
    )
    (comp (ref "R41")
      (value "RES_0603")
      (footprint "eagle-import:R0603")
      (libsource (lib "eagle-import") (part "RES_0603"))
    )
    (comp (ref "R42")
      (value "RES_0603")
      (footprint "eagle-import:R0603")
      (libsource (lib "eagle-import") (part "RES_0603"))
    )
    (comp (ref "R43")
      (value "RES_0603")
      (footprint "eagle-import:R0603")
      (libsource (lib "eagle-import") (part "RES_0603"))
    )
    (comp (ref "TP1")
      (value "TEST_POINT")
      (footprint "eagle-import:TP")
      (libsource (lib "eagle-import") (part "TEST_POINT"))
    )
    (comp (ref "TP2")
      (value "TEST_POINT")
      (footprint "eagle-import:TP")
      (libsource (lib "eagle-import") (part "TEST_POINT"))
    )
    (comp (ref "TP3")
      (value "TEST_POINT")
      (footprint "eagle-import:TP")
      (libsource (lib "eagle-import") (part "TEST_POINT"))
    )
    (comp (ref "TP4")
      (value "TEST_POINT")
      (footprint "eagle-import:TP")
      (libsource (lib "eagle-import") (part "TEST_POINT"))
    )
    (comp (ref "TP5")
      (value "TEST_POINT")
      (footprint "eagle-import:TP")
      (libsource (lib "eagle-import") (part "TEST_POINT"))
    )
    (comp (ref "TP6")
      (value "TEST_POINT")
      (footprint "eagle-import:TP")
      (libsource (lib "eagle-import") (part "TEST_POINT"))
    )
    (comp (ref "TP7")
      (value "TEST_POINT")
      (footprint "eagle-import:TP")
      (libsource (lib "eagle-import") (part "TEST_POINT"))
    )
    (comp (ref "TP8")
      (value "TEST_POINT")
      (footprint "eagle-import:TP")
      (libsource (lib "eagle-import") (part "TEST_POINT"))
    )
    (comp (ref "TP9")
      (value "TEST_POINT")
      (footprint "eagle-import:TP")
      (libsource (lib "eagle-import") (part "TEST_POINT"))
    )
    (comp (ref "TP10")
      (value "TEST_POINT")
      (footprint "eagle-import:TP")
      (libsource (lib "eagle-import") (part "TEST_POINT"))
    )
    (comp (ref "TP11")
      (value "TEST_POINT")
      (footprint "eagle-import:TP")
      (libsource (lib "eagle-import") (part "TEST_POINT"))
    )
    (comp (ref "TP12")
      (value "TEST_POINT")
      (footprint "eagle-import:TP")
      (libsource (lib "eagle-import") (part "TEST_POINT"))
    )
    (comp (ref "TP13")
      (value "TEST_POINT")
      (footprint "eagle-import:TP")
      (libsource (lib "eagle-import") (part "TEST_POINT"))
    )
    (comp (ref "TP14")
      (value "TEST_POINT")
      (footprint "eagle-import:TP")
      (libsource (lib "eagle-import") (part "TEST_POINT"))
    )
    (comp (ref "TP15")
      (value "TEST_POINT")
      (footprint "eagle-import:TP")
      (libsource (lib "eagle-import") (part "TEST_POINT"))
    )
    (comp (ref "TP16")
      (value "TEST_POINT")
      (footprint "eagle-import:TP")
      (libsource (lib "eagle-import") (part "TEST_POINT"))
    )
    (comp (ref "TP17")
      (value "TEST_POINT")
      (footprint "eagle-import:TP")
      (libsource (lib "eagle-import") (part "TEST_POINT"))
    )
    (comp (ref "TP18")
      (value "TEST_POINT")
      (footprint "eagle-import:TP")
      (libsource (lib "eagle-import") (part "TEST_POINT"))
    )
    (comp (ref "TP19")
      (value "TEST_POINT")
      (footprint "eagle-import:TP")
      (libsource (lib "eagle-import") (part "TEST_POINT"))
    )
    (comp (ref "TP20")
      (value "TEST_POINT")
      (footprint "eagle-import:TP")
      (libsource (lib "eagle-import") (part "TEST_POINT"))
    )
    (comp (ref "TP21")
      (value "TEST_POINT")
      (footprint "eagle-import:TP")
      (libsource (lib "eagle-import") (part "TEST_POINT"))
    )
    (comp (ref "TP22")
      (value "TEST_POINT")
      (footprint "eagle-import:TP")
      (libsource (lib "eagle-import") (part "TEST_POINT"))
    )
    (comp (ref "TP23")
      (value "TEST_POINT")
      (footprint "eagle-import:TP")
      (libsource (lib "eagle-import") (part "TEST_POINT"))
    )
    (comp (ref "TP24")
      (value "TEST_POINT")
      (footprint "eagle-import:TP")
      (libsource (lib "eagle-import") (part "TEST_POINT"))
    )
    (comp (ref "TP25")
      (value "TEST_POINT")
      (footprint "eagle-import:TP")
      (libsource (lib "eagle-import") (part "TEST_POINT"))
    )
    (comp (ref "TP26")
      (value "TEST_POINT")
      (footprint "eagle-import:TP")
      (libsource (lib "eagle-import") (part "TEST_POINT"))
    )
    (comp (ref "TP27")
      (value "TEST_POINT")
      (footprint "eagle-import:TP")
      (libsource (lib "eagle-import") (part "TEST_POINT"))
    )
    (comp (ref "TP28")
      (value "TEST_POINT")
      (footprint "eagle-import:TP")
      (libsource (lib "eagle-import") (part "TEST_POINT"))
    )
    (comp (ref "TP29")
      (value "TEST_POINT")
      (footprint "eagle-import:TP")
      (libsource (lib "eagle-import") (part "TEST_POINT"))
    )
    (comp (ref "TP30")
      (value "TEST_POINT")
      (footprint "eagle-import:TP")
      (libsource (lib "eagle-import") (part "TEST_POINT"))
    )
    (comp (ref "TP31")
      (value "TEST_POINT")
      (footprint "eagle-import:TP")
      (libsource (lib "eagle-import") (part "TEST_POINT"))
    )
    (comp (ref "TP32")
      (value "TEST_POINT")
      (footprint "eagle-import:TP")
      (libsource (lib "eagle-import") (part "TEST_POINT"))
    )
    (comp (ref "TP33")
      (value "TEST_POINT")
      (footprint "eagle-import:TP")
      (libsource (lib "eagle-import") (part "TEST_POINT"))
    )
    (comp (ref "TP34")
      (value "TEST_POINT")
      (footprint "eagle-import:TP")
      (libsource (lib "eagle-import") (part "TEST_POINT"))
    )
    (comp (ref "TP35")
      (value "TEST_POINT")
      (footprint "eagle-import:TP")
      (libsource (lib "eagle-import") (part "TEST_POINT"))
    )
    (comp (ref "TP36")
      (value "TEST_POINT")
      (footprint "eagle-import:TP")
      (libsource (lib "eagle-import") (part "TEST_POINT"))
    )
    (comp (ref "U$5")
      (value "MAX1072")
      (footprint "eagle-import:TQFN12")
      (libsource (lib "eagle-import") (part "MAX1072"))
    )
  )
  (nets
    (net (code "1") (name "/AGND") (class "Default")
      (node (ref "C10") (pin "2") (pinfunction "2_2") (pintype "passive"))
      (node (ref "C41") (pin "2") (pinfunction "2_2") (pintype "passive"))
      (node (ref "C6") (pin "2") (pinfunction "2_2") (pintype "passive"))
      (node (ref "C7") (pin "2") (pinfunction "2_2") (pintype "passive"))
      (node (ref "C9") (pin "2") (pinfunction "2_2") (pintype "passive"))
      (node (ref "IC1") (pin "1") (pinfunction "AGND_1") (pintype "power_in"))
      (node (ref "IC1") (pin "16") (pinfunction "AGND_16") (pintype "power_in"))
      (node (ref "IC1") (pin "17") (pinfunction "AGND_17") (pintype "power_in"))
      (node (ref "IC1") (pin "32") (pinfunction "AGND_32") (pintype "power_in"))
      (node (ref "IC1") (pin "33") (pinfunction "ANGD_33") (pintype "power_in"))
      (node (ref "IC1") (pin "48") (pinfunction "ANGD_48") (pintype "power_in"))
      (node (ref "IC1") (pin "49") (pinfunction "ANGD_49") (pintype "power_in"))
      (node (ref "IC1") (pin "58") (pinfunction "ANGD_58") (pintype "power_in"))
      (node (ref "IC1") (pin "64") (pinfunction "ANGD_64") (pintype "power_in"))
      (node (ref "IC13") (pin "2") (pinfunction "GND_2") (pintype "bidirectional"))
      (node (ref "JP2") (pin "2") (pinfunction "2_2") (pintype "passive"))
      (node (ref "JP6") (pin "2") (pinfunction "2_2") (pintype "passive"))
      (node (ref "TP19") (pin "TP") (pinfunction "TP_TP") (pintype "input"))
    )
    (net (code "2") (name "/AVDD") (class "Default")
      (node (ref "C10") (pin "1") (pinfunction "1_1") (pintype "passive"))
      (node (ref "C41") (pin "1") (pinfunction "1_1") (pintype "passive"))
      (node (ref "C6") (pin "1") (pinfunction "1_1") (pintype "passive"))
      (node (ref "C9") (pin "1") (pinfunction "1_1") (pintype "passive"))
      (node (ref "IC1") (pin "62") (pinfunction "AVDD_62") (pintype "power_in"))
      (node (ref "IC13") (pin "5") (pinfunction "VREF_5") (pintype "bidirectional"))
      (node (ref "TP7") (pin "TP") (pinfunction "TP_TP") (pintype "input"))
    )
    (net (code "3") (name "/BASELINE") (class "Default")
      (node (ref "IC1") (pin "56") (pinfunction "BASELINE_56") (pintype "output"))
      (node (ref "TP10") (pin "TP") (pinfunction "TP_TP") (pintype "input"))
    )
    (net (code "4") (name "/CAP_PRECHAR") (class "Default")
      (node (ref "C38") (pin "2") (pinfunction "2_2") (pintype "passive"))
      (node (ref "IC1") (pin "14") (pinfunction "CAP_PRECHARGE_EXT_14") (pintype "input"))
      (node (ref "TP21") (pin "TP") (pinfunction "TP_TP") (pintype "input"))
    )
    (net (code "5") (name "/CAP_PRECHAR_1") (class "Default")
      (node (ref "C57") (pin "1") (pinfunction "1_1") (pintype "passive"))
      (node (ref "IC21") (pin "12") (pinfunction "D4_12") (pintype "bidirectional"))
      (node (ref "JP1") (pin "1") (pinfunction "1_1") (pintype "passive"))
    )
    (net (code "6") (name "/CLK") (class "Default")
      (node (ref "IC1") (pin "20") (pinfunction "CLK_20") (pintype "bidirectional"))
      (node (ref "R30") (pin "1") (pinfunction "1_1") (pintype "passive"))
      (node (ref "R31") (pin "2") (pinfunction "2_2") (pintype "passive"))
    )
    (net (code "7") (name "/CLK_ADC") (class "Default")
      (node (ref "J1") (pin "A44") (pinfunction "A44_A44") (pintype "bidirectional"))
    )
    (net (code "8") (name "/CLK_ADC1") (class "Default")
      (node (ref "IC22") (pin "P$10") (pinfunction "SCLK_P$10") (pintype "bidirectional"))
    )
    (net (code "9") (name "/CLK_ADC2") (class "Default")
      (node (ref "U$5") (pin "P$10") (pinfunction "SCLK_P$10") (pintype "bidirectional"))
    )
    (net (code "10") (name "/CLK_DAC") (class "Default")
      (node (ref "IC23") (pin "10") (pinfunction "SCLK_10") (pintype "bidirectional"))
      (node (ref "J1") (pin "A17") (pinfunction "A17_A17") (pintype "bidirectional"))
    )
    (net (code "11") (name "/CLK_PRECH1") (class "Default")
      (node (ref "IC1") (pin "9") (pinfunction "CLK_PRECH1_9") (pintype "bidirectional"))
      (node (ref "R40") (pin "1") (pinfunction "1_1") (pintype "passive"))
      (node (ref "R41") (pin "2") (pinfunction "2_2") (pintype "passive"))
    )
    (net (code "12") (name "/CLK_PRECH1_T") (class "Default")
      (node (ref "J1") (pin "A39") (pinfunction "A39_A39") (pintype "bidirectional"))
      (node (ref "R40") (pin "2") (pinfunction "2_2") (pintype "passive"))
    )
    (net (code "13") (name "/CLK_PRECH2") (class "Default")
      (node (ref "IC1") (pin "10") (pinfunction "CLK_PRECH2_10") (pintype "bidirectional"))
      (node (ref "R42") (pin "1") (pinfunction "1_1") (pintype "passive"))
      (node (ref "R43") (pin "2") (pinfunction "2_2") (pintype "passive"))
    )
    (net (code "14") (name "/CLK_PRECH2_T") (class "Default")
      (node (ref "J1") (pin "A35") (pinfunction "A35_A35") (pintype "bidirectional"))
      (node (ref "R42") (pin "2") (pinfunction "2_2") (pintype "passive"))
    )
    (net (code "15") (name "/CLK_REF") (class "Default")
      (node (ref "IC18") (pin "4") (pinfunction "CLK_4") (pintype "bidirectional"))
      (node (ref "IC19") (pin "4") (pinfunction "CLK_4") (pintype "bidirectional"))
      (node (ref "IC20") (pin "4") (pinfunction "CLK_4") (pintype "bidirectional"))
      (node (ref "J1") (pin "A9") (pinfunction "A9_A9") (pintype "bidirectional"))
    )
    (net (code "16") (name "/CLK_T") (class "Default")
      (node (ref "J1") (pin "A21") (pinfunction "A21_A21") (pintype "bidirectional"))
      (node (ref "R30") (pin "2") (pinfunction "2_2") (pintype "passive"))
    )
    (net (code "17") (name "/CS_B0") (class "Default")
      (node (ref "IC1") (pin "41") (pinfunction "CS_B0_41") (pintype "bidirectional"))
      (node (ref "R14") (pin "1") (pinfunction "1_1") (pintype "passive"))
      (node (ref "R15") (pin "2") (pinfunction "2_2") (pintype "passive"))
    )
    (net (code "18") (name "/CS_B0_T") (class "Default")
      (node (ref "J1") (pin "A26") (pinfunction "A26_A26") (pintype "bidirectional"))
      (node (ref "R14") (pin "2") (pinfunction "2_2") (pintype "passive"))
    )
    (net (code "19") (name "/CS_B1") (class "Default")
      (node (ref "IC1") (pin "42") (pinfunction "CS_B1_42") (pintype "bidirectional"))
      (node (ref "R16") (pin "1") (pinfunction "1_1") (pintype "passive"))
      (node (ref "R17") (pin "2") (pinfunction "2_2") (pintype "passive"))
    )
    (net (code "20") (name "/CS_B1_T") (class "Default")
      (node (ref "J1") (pin "A28") (pinfunction "A28_A28") (pintype "bidirectional"))
      (node (ref "R16") (pin "2") (pinfunction "2_2") (pintype "passive"))
    )
    (net (code "21") (name "/CS_B2") (class "Default")
      (node (ref "IC1") (pin "43") (pinfunction "CS_B2_43") (pintype "bidirectional"))
      (node (ref "R18") (pin "1") (pinfunction "1_1") (pintype "passive"))
      (node (ref "R19") (pin "2") (pinfunction "2_2") (pintype "passive"))
    )
    (net (code "22") (name "/CS_B2_T") (class "Default")
      (node (ref "J1") (pin "A30") (pinfunction "A30_A30") (pintype "bidirectional"))
      (node (ref "R18") (pin "2") (pinfunction "2_2") (pintype "passive"))
    )
    (net (code "23") (name "/CS_B3") (class "Default")
      (node (ref "IC1") (pin "44") (pinfunction "CS_B3_44") (pintype "bidirectional"))
      (node (ref "R20") (pin "1") (pinfunction "1_1") (pintype "passive"))
      (node (ref "R21") (pin "2") (pinfunction "2_2") (pintype "passive"))
    )
    (net (code "24") (name "/CS_B3_T") (class "Default")
      (node (ref "J1") (pin "A32") (pinfunction "A32_A32") (pintype "bidirectional"))
      (node (ref "R20") (pin "2") (pinfunction "2_2") (pintype "passive"))
    )
    (net (code "25") (name "/CS_B4") (class "Default")
      (node (ref "IC1") (pin "45") (pinfunction "CS_B4_45") (pintype "bidirectional"))
      (node (ref "R22") (pin "1") (pinfunction "1_1") (pintype "passive"))
      (node (ref "R23") (pin "2") (pinfunction "2_2") (pintype "passive"))
    )
    (net (code "26") (name "/CS_B4_T") (class "Default")
      (node (ref "J1") (pin "A36") (pinfunction "A36_A36") (pintype "bidirectional"))
      (node (ref "R22") (pin "2") (pinfunction "2_2") (pintype "passive"))
    )
    (net (code "27") (name "/CS_B5") (class "Default")
      (node (ref "IC1") (pin "46") (pinfunction "CS_B5_46") (pintype "bidirectional"))
      (node (ref "R24") (pin "1") (pinfunction "1_1") (pintype "passive"))
      (node (ref "R25") (pin "2") (pinfunction "2_2") (pintype "passive"))
    )
    (net (code "28") (name "/CS_B5_T") (class "Default")
      (node (ref "J1") (pin "A38") (pinfunction "A38_A38") (pintype "bidirectional"))
      (node (ref "R24") (pin "2") (pinfunction "2_2") (pintype "passive"))
    )
    (net (code "29") (name "/CS_REF_1") (class "Default")
      (node (ref "IC18") (pin "6") (pinfunction "CS~{}_6") (pintype "bidirectional"))
      (node (ref "J1") (pin "A13") (pinfunction "A13_A13") (pintype "bidirectional"))
    )
    (net (code "30") (name "/CS_REF_2") (class "Default")
      (node (ref "IC19") (pin "6") (pinfunction "CS~{}_6") (pintype "bidirectional"))
      (node (ref "J1") (pin "A11") (pinfunction "A11_A11") (pintype "bidirectional"))
    )
    (net (code "31") (name "/CS_REF_3") (class "Default")
      (node (ref "IC20") (pin "6") (pinfunction "CS~{}_6") (pintype "bidirectional"))
      (node (ref "J1") (pin "A8") (pinfunction "A8_A8") (pintype "bidirectional"))
    )
    (net (code "32") (name "/DGND") (class "Default")
      (node (ref "C11") (pin "2") (pinfunction "2_2") (pintype "passive"))
      (node (ref "C12") (pin "2") (pinfunction "2_2") (pintype "passive"))
      (node (ref "C13") (pin "2") (pinfunction "2_2") (pintype "passive"))
      (node (ref "C40") (pin "2") (pinfunction "2_2") (pintype "passive"))
      (node (ref "C5") (pin "2") (pinfunction "2_2") (pintype "passive"))
      (node (ref "IC1") (pin "28") (pinfunction "DGND_28") (pintype "power_in"))
      (node (ref "IC10") (pin "2") (pinfunction "GND_2") (pintype "bidirectional"))
      (node (ref "JP6") (pin "1") (pinfunction "1_1") (pintype "passive"))
      (node (ref "TP29") (pin "TP") (pinfunction "TP_TP") (pintype "input"))
    )
    (net (code "33") (name "/DVDD") (class "Default")
      (node (ref "C11") (pin "1") (pinfunction "1_1") (pintype "passive"))
      (node (ref "C12") (pin "1") (pinfunction "1_1") (pintype "passive"))
      (node (ref "C13") (pin "1") (pinfunction "1_1") (pintype "passive"))
      (node (ref "C40") (pin "1") (pinfunction "1_1") (pintype "passive"))
      (node (ref "IC1") (pin "27") (pinfunction "DVDD_27") (pintype "power_in"))
      (node (ref "IC10") (pin "5") (pinfunction "VREF_5") (pintype "bidirectional"))
      (node (ref "TP8") (pin "TP") (pinfunction "TP_TP") (pintype "input"))
    )
    (net (code "34") (name "/GND") (class "Default")
      (node (ref "C1") (pin "2") (pinfunction "2_2") (pintype "passive"))
      (node (ref "C14") (pin "2") (pinfunction "2_2") (pintype "passive"))
      (node (ref "C15") (pin "2") (pinfunction "2_2") (pintype "passive"))
      (node (ref "C16") (pin "2") (pinfunction "2_2") (pintype "passive"))
      (node (ref "C17") (pin "2") (pinfunction "2_2") (pintype "passive"))
      (node (ref "C18") (pin "2") (pinfunction "2_2") (pintype "passive"))
      (node (ref "C19") (pin "2") (pinfunction "2_2") (pintype "passive"))
      (node (ref "C2") (pin "2") (pinfunction "2_2") (pintype "passive"))
      (node (ref "C20") (pin "2") (pinfunction "2_2") (pintype "passive"))
      (node (ref "C21") (pin "2") (pinfunction "2_2") (pintype "passive"))
      (node (ref "C22") (pin "2") (pinfunction "2_2") (pintype "passive"))
      (node (ref "C23") (pin "2") (pinfunction "2_2") (pintype "passive"))
      (node (ref "C24") (pin "2") (pinfunction "2_2") (pintype "passive"))
      (node (ref "C25") (pin "2") (pinfunction "2_2") (pintype "passive"))
      (node (ref "C26") (pin "2") (pinfunction "2_2") (pintype "passive"))
      (node (ref "C27") (pin "2") (pinfunction "2_2") (pintype "passive"))
      (node (ref "C28") (pin "2") (pinfunction "2_2") (pintype "passive"))
      (node (ref "C29") (pin "2") (pinfunction "2_2") (pintype "passive"))
      (node (ref "C3") (pin "2") (pinfunction "2_2") (pintype "passive"))
      (node (ref "C30") (pin "2") (pinfunction "2_2") (pintype "passive"))
      (node (ref "C31") (pin "2") (pinfunction "2_2") (pintype "passive"))
      (node (ref "C32") (pin "2") (pinfunction "2_2") (pintype "passive"))
      (node (ref "C33") (pin "2") (pinfunction "2_2") (pintype "passive"))
      (node (ref "C34") (pin "2") (pinfunction "2_2") (pintype "passive"))
      (node (ref "C35") (pin "2") (pinfunction "2_2") (pintype "passive"))
      (node (ref "C39") (pin "1") (pinfunction "1_1") (pintype "passive"))
      (node (ref "C4") (pin "2") (pinfunction "2_2") (pintype "passive"))
      (node (ref "C42") (pin "2") (pinfunction "2_2") (pintype "passive"))
      (node (ref "C43") (pin "2") (pinfunction "2_2") (pintype "passive"))
      (node (ref "C44") (pin "2") (pinfunction "2_2") (pintype "passive"))
      (node (ref "C45") (pin "2") (pinfunction "2_2") (pintype "passive"))
      (node (ref "C46") (pin "2") (pinfunction "2_2") (pintype "passive"))
      (node (ref "C47") (pin "2") (pinfunction "2_2") (pintype "passive"))
      (node (ref "C48") (pin "2") (pinfunction "2_2") (pintype "passive"))
      (node (ref "C49") (pin "2") (pinfunction "2_2") (pintype "passive"))
      (node (ref "C50") (pin "2") (pinfunction "2_2") (pintype "passive"))
      (node (ref "C51") (pin "2") (pinfunction "2_2") (pintype "passive"))
      (node (ref "C52") (pin "2") (pinfunction "2_2") (pintype "passive"))
      (node (ref "C53") (pin "2") (pinfunction "2_2") (pintype "passive"))
      (node (ref "C54") (pin "2") (pinfunction "2_2") (pintype "passive"))
      (node (ref "C55") (pin "2") (pinfunction "2_2") (pintype "passive"))
      (node (ref "C56") (pin "2") (pinfunction "2_2") (pintype "passive"))
      (node (ref "C57") (pin "2") (pinfunction "2_2") (pintype "passive"))
      (node (ref "C8") (pin "2") (pinfunction "2_2") (pintype "passive"))
      (node (ref "IC11") (pin "2") (pinfunction "GND_2") (pintype "passive"))
      (node (ref "IC12") (pin "4") (pinfunction "V-_4") (pintype "bidirectional"))
      (node (ref "IC14") (pin "4") (pinfunction "V-_4") (pintype "bidirectional"))
      (node (ref "IC16") (pin "2") (pinfunction "GND_2") (pintype "bidirectional"))
      (node (ref "IC17") (pin "2") (pinfunction "GND_2") (pintype "bidirectional"))
      (node (ref "IC18") (pin "3") (pinfunction "GND_3") (pintype "bidirectional"))
      (node (ref "IC18") (pin "8") (pinfunction "A_8") (pintype "bidirectional"))
      (node (ref "IC19") (pin "3") (pinfunction "GND_3") (pintype "bidirectional"))
      (node (ref "IC19") (pin "8") (pinfunction "A_8") (pintype "bidirectional"))
      (node (ref "IC2") (pin "2") (pinfunction "GND_2") (pintype "bidirectional"))
      (node (ref "IC20") (pin "3") (pinfunction "GND_3") (pintype "bidirectional"))
      (node (ref "IC20") (pin "8") (pinfunction "A_8") (pintype "bidirectional"))
      (node (ref "IC21") (pin "10") (pinfunction "S3B_10") (pintype "bidirectional"))
      (node (ref "IC21") (pin "13") (pinfunction "S4B_13") (pintype "bidirectional"))
      (node (ref "IC21") (pin "8") (pinfunction "GND_8") (pintype "bidirectional"))
      (node (ref "IC22") (pin "P$3") (pinfunction "RGND_P$3") (pintype "bidirectional"))
      (node (ref "IC22") (pin "P$6") (pinfunction "GND_P$6") (pintype "bidirectional"))
      (node (ref "IC23") (pin "3") (pinfunction "GND_3") (pintype "bidirectional"))
      (node (ref "IC3") (pin "2") (pinfunction "GND_2") (pintype "bidirectional"))
      (node (ref "IC4") (pin "2") (pinfunction "GND_2") (pintype "bidirectional"))
      (node (ref "IC5") (pin "2") (pinfunction "GND_2") (pintype "bidirectional"))
      (node (ref "IC6") (pin "2") (pinfunction "GND_2") (pintype "bidirectional"))
      (node (ref "IC7") (pin "2") (pinfunction "GND_2") (pintype "bidirectional"))
      (node (ref "IC8") (pin "2") (pinfunction "GND_2") (pintype "bidirectional"))
      (node (ref "IC9") (pin "2") (pinfunction "GND_2") (pintype "passive"))
      (node (ref "J1") (pin "B10") (pinfunction "B10_B10") (pintype "bidirectional"))
      (node (ref "J1") (pin "B11") (pinfunction "B11_B11") (pintype "bidirectional"))
      (node (ref "J1") (pin "B12") (pinfunction "B12_B12") (pintype "bidirectional"))
      (node (ref "J1") (pin "B13") (pinfunction "B13_B13") (pintype "bidirectional"))
      (node (ref "J1") (pin "B14") (pinfunction "B14_B14") (pintype "bidirectional"))
      (node (ref "J1") (pin "B15") (pinfunction "B15_B15") (pintype "bidirectional"))
      (node (ref "J1") (pin "B16") (pinfunction "B16_B16") (pintype "bidirectional"))
      (node (ref "J1") (pin "B17") (pinfunction "B17_B17") (pintype "bidirectional"))
      (node (ref "J1") (pin "B18") (pinfunction "B18_B18") (pintype "bidirectional"))
      (node (ref "J1") (pin "B19") (pinfunction "B19_B19") (pintype "bidirectional"))
      (node (ref "J1") (pin "B2") (pinfunction "B2_B2") (pintype "bidirectional"))
      (node (ref "J1") (pin "B20") (pinfunction "B20_B20") (pintype "bidirectional"))
      (node (ref "J1") (pin "B21") (pinfunction "B21_B21") (pintype "bidirectional"))
      (node (ref "J1") (pin "B22") (pinfunction "B22_B22") (pintype "bidirectional"))
      (node (ref "J1") (pin "B23") (pinfunction "B23_B23") (pintype "bidirectional"))
      (node (ref "J1") (pin "B24") (pinfunction "B24_B24") (pintype "bidirectional"))
      (node (ref "J1") (pin "B25") (pinfunction "B25_B25") (pintype "bidirectional"))
      (node (ref "J1") (pin "B26") (pinfunction "B26_B26") (pintype "bidirectional"))
      (node (ref "J1") (pin "B27") (pinfunction "B27_B27") (pintype "bidirectional"))
      (node (ref "J1") (pin "B28") (pinfunction "B28_B28") (pintype "bidirectional"))
      (node (ref "J1") (pin "B29") (pinfunction "B29_B29") (pintype "bidirectional"))
      (node (ref "J1") (pin "B30") (pinfunction "B30_B30") (pintype "bidirectional"))
      (node (ref "J1") (pin "B31") (pinfunction "B31_B31") (pintype "bidirectional"))
      (node (ref "J1") (pin "B32") (pinfunction "B32_B32") (pintype "bidirectional"))
      (node (ref "J1") (pin "B33") (pinfunction "B33_B33") (pintype "bidirectional"))
      (node (ref "J1") (pin "B34") (pinfunction "B34_B34") (pintype "bidirectional"))
      (node (ref "J1") (pin "B35") (pinfunction "B35_B35") (pintype "bidirectional"))
      (node (ref "J1") (pin "B36") (pinfunction "B36_B36") (pintype "bidirectional"))
      (node (ref "J1") (pin "B37") (pinfunction "B37_B37") (pintype "bidirectional"))
      (node (ref "J1") (pin "B38") (pinfunction "B38_B38") (pintype "bidirectional"))
      (node (ref "J1") (pin "B39") (pinfunction "B39_B39") (pintype "bidirectional"))
      (node (ref "J1") (pin "B40") (pinfunction "B40_B40") (pintype "bidirectional"))
      (node (ref "J1") (pin "B41") (pinfunction "B41_B41") (pintype "bidirectional"))
      (node (ref "J1") (pin "B42") (pinfunction "B42_B42") (pintype "bidirectional"))
      (node (ref "J1") (pin "B43") (pinfunction "B43_B43") (pintype "bidirectional"))
      (node (ref "J1") (pin "B44") (pinfunction "B44_B44") (pintype "bidirectional"))
      (node (ref "J1") (pin "B45") (pinfunction "B45_B45") (pintype "bidirectional"))
      (node (ref "J1") (pin "B47") (pinfunction "B47_B47") (pintype "bidirectional"))
      (node (ref "J1") (pin "B5") (pinfunction "B5_B5") (pintype "bidirectional"))
      (node (ref "J1") (pin "B6") (pinfunction "B6_B6") (pintype "bidirectional"))
      (node (ref "J1") (pin "B7") (pinfunction "B7_B7") (pintype "bidirectional"))
      (node (ref "J1") (pin "B8") (pinfunction "B8_B8") (pintype "bidirectional"))
      (node (ref "J1") (pin "B9") (pinfunction "B9_B9") (pintype "bidirectional"))
      (node (ref "JP2") (pin "1") (pinfunction "1_1") (pintype "passive"))
      (node (ref "JP3") (pin "1") (pinfunction "1_1") (pintype "passive"))
      (node (ref "R15") (pin "1") (pinfunction "1_1") (pintype "passive"))
      (node (ref "R17") (pin "1") (pinfunction "1_1") (pintype "passive"))
      (node (ref "R19") (pin "1") (pinfunction "1_1") (pintype "passive"))
      (node (ref "R2") (pin "3") (pinfunction "3_3") (pintype "passive"))
      (node (ref "R21") (pin "1") (pinfunction "1_1") (pintype "passive"))
      (node (ref "R23") (pin "1") (pinfunction "1_1") (pintype "passive"))
      (node (ref "R25") (pin "1") (pinfunction "1_1") (pintype "passive"))
      (node (ref "R27") (pin "1") (pinfunction "1_1") (pintype "passive"))
      (node (ref "R29") (pin "1") (pinfunction "1_1") (pintype "passive"))
      (node (ref "R31") (pin "1") (pinfunction "1_1") (pintype "passive"))
      (node (ref "R33") (pin "1") (pinfunction "1_1") (pintype "passive"))
      (node (ref "R35") (pin "1") (pinfunction "1_1") (pintype "passive"))
      (node (ref "R37") (pin "1") (pinfunction "1_1") (pintype "passive"))
      (node (ref "R39") (pin "1") (pinfunction "1_1") (pintype "passive"))
      (node (ref "R4") (pin "3") (pinfunction "3_3") (pintype "passive"))
      (node (ref "R41") (pin "1") (pinfunction "1_1") (pintype "passive"))
      (node (ref "R43") (pin "1") (pinfunction "1_1") (pintype "passive"))
      (node (ref "R5") (pin "3") (pinfunction "3_3") (pintype "passive"))
      (node (ref "R6") (pin "3") (pinfunction "3_3") (pintype "passive"))
      (node (ref "R8") (pin "1") (pinfunction "1_1") (pintype "passive"))
      (node (ref "R9") (pin "1") (pinfunction "1_1") (pintype "passive"))
      (node (ref "TP18") (pin "TP") (pinfunction "TP_TP") (pintype "input"))
      (node (ref "TP31") (pin "TP") (pinfunction "TP_TP") (pintype "input"))
      (node (ref "TP32") (pin "TP") (pinfunction "TP_TP") (pintype "input"))
      (node (ref "TP33") (pin "TP") (pinfunction "TP_TP") (pintype "input"))
      (node (ref "TP34") (pin "TP") (pinfunction "TP_TP") (pintype "input"))
      (node (ref "TP35") (pin "TP") (pinfunction "TP_TP") (pintype "input"))
      (node (ref "TP36") (pin "TP") (pinfunction "TP_TP") (pintype "input"))
      (node (ref "U$5") (pin "P$3") (pinfunction "RGND_P$3") (pintype "bidirectional"))
      (node (ref "U$5") (pin "P$6") (pinfunction "GND_P$6") (pintype "bidirectional"))
    )
    (net (code "35") (name "/HOLD") (class "Default")
      (node (ref "IC1") (pin "37") (pinfunction "HOLD_37") (pintype "bidirectional"))
      (node (ref "R38") (pin "1") (pinfunction "1_1") (pintype "passive"))
      (node (ref "R39") (pin "2") (pinfunction "2_2") (pintype "passive"))
    )
    (net (code "36") (name "/HOLD_T") (class "Default")
      (node (ref "J1") (pin "A24") (pinfunction "A24_A24") (pintype "bidirectional"))
      (node (ref "R38") (pin "2") (pinfunction "2_2") (pintype "passive"))
    )
    (net (code "37") (name "/MUX_DAC_EN") (class "Default")
      (node (ref "IC21") (pin "15") (pinfunction "~{EN}_15") (pintype "bidirectional"))
      (node (ref "J1") (pin "A20") (pinfunction "A20_A20") (pintype "bidirectional"))
    )
    (net (code "38") (name "/MUX_DAC_SEL") (class "Default")
      (node (ref "IC21") (pin "1") (pinfunction "IN_1") (pintype "bidirectional"))
      (node (ref "J1") (pin "A19") (pinfunction "A19_A19") (pintype "bidirectional"))
    )
    (net (code "39") (name "/MUX_REF_1") (class "Default")
      (node (ref "IC2") (pin "6") (pinfunction "IN_6") (pintype "bidirectional"))
      (node (ref "J1") (pin "A12") (pinfunction "A12_A12") (pintype "bidirectional"))
    )
    (net (code "40") (name "/MUX_REF_2") (class "Default")
      (node (ref "IC3") (pin "6") (pinfunction "IN_6") (pintype "bidirectional"))
      (node (ref "J1") (pin "A10") (pinfunction "A10_A10") (pintype "bidirectional"))
    )
    (net (code "41") (name "/MUX_REF_3") (class "Default")
      (node (ref "IC4") (pin "6") (pinfunction "IN_6") (pintype "bidirectional"))
      (node (ref "J1") (pin "A6") (pinfunction "A6_A6") (pintype "bidirectional"))
    )
    (net (code "42") (name "/OP_MODE") (class "Default")
      (node (ref "IC1") (pin "11") (pinfunction "OP_MODE_11") (pintype "bidirectional"))
      (node (ref "R26") (pin "1") (pinfunction "1_1") (pintype "passive"))
      (node (ref "R27") (pin "2") (pinfunction "2_2") (pintype "passive"))
    )
    (net (code "43") (name "/OP_MODE_T") (class "Default")
      (node (ref "J1") (pin "A34") (pinfunction "A34_A34") (pintype "bidirectional"))
      (node (ref "R26") (pin "2") (pinfunction "2_2") (pintype "passive"))
    )
    (net (code "44") (name "/OUT_S") (class "Default")
      (node (ref "IC1") (pin "35") (pinfunction "OUT_S_35") (pintype "bidirectional"))
      (node (ref "R32") (pin "1") (pinfunction "1_1") (pintype "passive"))
      (node (ref "R33") (pin "2") (pinfunction "2_2") (pintype "passive"))
    )
    (net (code "45") (name "/OUT_S_T") (class "Default")
      (node (ref "J1") (pin "A22") (pinfunction "A22_A22") (pintype "bidirectional"))
      (node (ref "R32") (pin "2") (pinfunction "2_2") (pintype "passive"))
    )
    (net (code "46") (name "/POT_R1") (class "Default")
      (node (ref "JP4") (pin "3") (pinfunction "3_3") (pintype "passive"))
      (node (ref "R1") (pin "2") (pinfunction "2_2") (pintype "passive"))
      (node (ref "R1") (pin "3") (pinfunction "3_3") (pintype "passive"))
      (node (ref "TP27") (pin "TP") (pinfunction "TP_TP") (pintype "input"))
    )
    (net (code "47") (name "/POT_R2") (class "Default")
      (node (ref "JP4") (pin "1") (pinfunction "1_1") (pintype "passive"))
      (node (ref "R2") (pin "1") (pinfunction "1_1") (pintype "passive"))
      (node (ref "R2") (pin "2") (pinfunction "2_2") (pintype "passive"))
      (node (ref "TP28") (pin "TP") (pinfunction "TP_TP") (pintype "input"))
    )
    (net (code "48") (name "/POT_R4") (class "Default")
      (node (ref "IC2") (pin "3") (pinfunction "A1_3") (pintype "bidirectional"))
      (node (ref "R4") (pin "2") (pinfunction "2_2") (pintype "passive"))
      (node (ref "TP24") (pin "TP") (pinfunction "TP_TP") (pintype "input"))
    )
    (net (code "49") (name "/POT_R5") (class "Default")
      (node (ref "IC3") (pin "3") (pinfunction "A1_3") (pintype "bidirectional"))
      (node (ref "R5") (pin "2") (pinfunction "2_2") (pintype "passive"))
      (node (ref "TP25") (pin "TP") (pinfunction "TP_TP") (pintype "input"))
    )
    (net (code "50") (name "/POT_R6") (class "Default")
      (node (ref "IC4") (pin "3") (pinfunction "A1_3") (pintype "bidirectional"))
      (node (ref "R6") (pin "2") (pinfunction "2_2") (pintype "passive"))
      (node (ref "TP26") (pin "TP") (pinfunction "TP_TP") (pintype "input"))
    )
    (net (code "51") (name "/REFIN_DAC") (class "Default")
      (node (ref "C28") (pin "1") (pinfunction "1_1") (pintype "passive"))
      (node (ref "IC23") (pin "6") (pinfunction "REFIN_6") (pintype "bidirectional"))
      (node (ref "IC8") (pin "5") (pinfunction "VREF_5") (pintype "bidirectional"))
      (node (ref "TP15") (pin "TP") (pinfunction "TP_TP") (pintype "input"))
    )
    (net (code "52") (name "/REF_ADC") (class "Default")
      (node (ref "C17") (pin "1") (pinfunction "1_1") (pintype "passive"))
      (node (ref "C18") (pin "1") (pinfunction "1_1") (pintype "passive"))
      (node (ref "C23") (pin "1") (pinfunction "1_1") (pintype "passive"))
      (node (ref "C24") (pin "1") (pinfunction "1_1") (pintype "passive"))
      (node (ref "C31") (pin "1") (pinfunction "1_1") (pintype "passive"))
      (node (ref "IC17") (pin "5") (pinfunction "VREF_5") (pintype "bidirectional"))
      (node (ref "IC22") (pin "P$2") (pinfunction "REF_P$2") (pintype "bidirectional"))
      (node (ref "TP17") (pin "TP") (pinfunction "TP_TP") (pintype "input"))
      (node (ref "U$5") (pin "P$2") (pinfunction "REF_P$2") (pintype "bidirectional"))
    )
    (net (code "53") (name "/RES_BIAS_EXT") (class "Default")
      (node (ref "IC1") (pin "6") (pinfunction "RES_BIAS_EXT_6") (pintype "bidirectional"))
      (node (ref "JP4") (pin "2") (pinfunction "2_2") (pintype "passive"))
    )
    (net (code "54") (name "/RST") (class "Default")
      (node (ref "IC1") (pin "38") (pinfunction "RST_38") (pintype "bidirectional"))
      (node (ref "R36") (pin "1") (pinfunction "1_1") (pintype "passive"))
      (node (ref "R37") (pin "2") (pinfunction "2_2") (pintype "passive"))
    )
    (net (code "55") (name "/RST_CSA") (class "Default")
      (node (ref "IC1") (pin "12") (pinfunction "RST_CSA_12") (pintype "bidirectional"))
      (node (ref "R28") (pin "1") (pinfunction "1_1") (pintype "passive"))
      (node (ref "R29") (pin "2") (pinfunction "2_2") (pintype "passive"))
    )
    (net (code "56") (name "/RST_CSA_T") (class "Default")
      (node (ref "J1") (pin "A25") (pinfunction "A25_A25") (pintype "bidirectional"))
      (node (ref "R28") (pin "2") (pinfunction "2_2") (pintype "passive"))
    )
    (net (code "57") (name "/RST_T") (class "Default")
      (node (ref "J1") (pin "A27") (pinfunction "A27_A27") (pintype "bidirectional"))
      (node (ref "R36") (pin "2") (pinfunction "2_2") (pintype "passive"))
    )
    (net (code "58") (name "/SDI_DAC") (class "Default")
      (node (ref "IC23") (pin "9") (pinfunction "DIN_9") (pintype "bidirectional"))
      (node (ref "J1") (pin "A15") (pinfunction "A15_A15") (pintype "bidirectional"))
    )
    (net (code "59") (name "/SDI_REF") (class "Default")
      (node (ref "IC18") (pin "5") (pinfunction "SDI_5") (pintype "bidirectional"))
      (node (ref "IC19") (pin "5") (pinfunction "SDI_5") (pintype "bidirectional"))
      (node (ref "IC20") (pin "5") (pinfunction "SDI_5") (pintype "bidirectional"))
      (node (ref "J1") (pin "A7") (pinfunction "A7_A7") (pintype "bidirectional"))
    )
    (net (code "60") (name "/SDO_ADC1") (class "Default")
      (node (ref "IC22") (pin "P$8") (pinfunction "DOUT_P$8") (pintype "bidirectional"))
      (node (ref "J1") (pin "A40") (pinfunction "A40_A40") (pintype "bidirectional"))
    )
    (net (code "61") (name "/SDO_ADC2") (class "Default")
      (node (ref "J1") (pin "A16") (pinfunction "A16_A16") (pintype "bidirectional"))
      (node (ref "U$5") (pin "P$8") (pinfunction "DOUT_P$8") (pintype "bidirectional"))
    )
    (net (code "62") (name "/SGN") (class "Default")
      (node (ref "IC1") (pin "39") (pinfunction "SGN_39") (pintype "bidirectional"))
      (node (ref "R34") (pin "1") (pinfunction "1_1") (pintype "passive"))
      (node (ref "R35") (pin "2") (pinfunction "2_2") (pintype "passive"))
    )
    (net (code "63") (name "/SGN_T") (class "Default")
      (node (ref "J1") (pin "A31") (pinfunction "A31_A31") (pintype "bidirectional"))
      (node (ref "R34") (pin "2") (pinfunction "2_2") (pintype "passive"))
    )
    (net (code "64") (name "/V0NDAC") (class "Default")
      (node (ref "C51") (pin "1") (pinfunction "1_1") (pintype "passive"))
      (node (ref "IC21") (pin "5") (pinfunction "S2A_5") (pintype "bidirectional"))
      (node (ref "IC23") (pin "2") (pinfunction "VOUTB_2") (pintype "bidirectional"))
    )
    (net (code "65") (name "/V0PDAC") (class "Default")
      (node (ref "C50") (pin "1") (pinfunction "1_1") (pintype "passive"))
      (node (ref "IC21") (pin "2") (pinfunction "S1A_2") (pintype "bidirectional"))
      (node (ref "IC23") (pin "1") (pinfunction "VOUTA_1") (pintype "bidirectional"))
    )
    (net (code "66") (name "/V1NDAC") (class "Default")
      (node (ref "C53") (pin "1") (pinfunction "1_1") (pintype "passive"))
      (node (ref "IC21") (pin "14") (pinfunction "S4A_14") (pintype "bidirectional"))
      (node (ref "IC23") (pin "5") (pinfunction "VOUTD_5") (pintype "bidirectional"))
    )
    (net (code "67") (name "/V1PDAC") (class "Default")
      (node (ref "C52") (pin "1") (pinfunction "1_1") (pintype "passive"))
      (node (ref "IC21") (pin "11") (pinfunction "S3A_11") (pintype "bidirectional"))
      (node (ref "IC23") (pin "4") (pinfunction "VOUTC_4") (pintype "bidirectional"))
    )
    (net (code "68") (name "/VDD") (class "Default")
      (node (ref "C1") (pin "1") (pinfunction "1_1") (pintype "passive"))
      (node (ref "C15") (pin "1") (pinfunction "1_1") (pintype "passive"))
      (node (ref "C16") (pin "1") (pinfunction "1_1") (pintype "passive"))
      (node (ref "C19") (pin "1") (pinfunction "1_1") (pintype "passive"))
      (node (ref "C2") (pin "1") (pinfunction "1_1") (pintype "passive"))
      (node (ref "C20") (pin "1") (pinfunction "1_1") (pintype "passive"))
      (node (ref "C25") (pin "1") (pinfunction "1_1") (pintype "passive"))
      (node (ref "C3") (pin "1") (pinfunction "1_1") (pintype "passive"))
      (node (ref "C30") (pin "1") (pinfunction "1_1") (pintype "passive"))
      (node (ref "C39") (pin "2") (pinfunction "2_2") (pintype "passive"))
      (node (ref "C4") (pin "1") (pinfunction "1_1") (pintype "passive"))
      (node (ref "C44") (pin "1") (pinfunction "1_1") (pintype "passive"))
      (node (ref "IC11") (pin "3") (pinfunction "VO_3") (pintype "passive"))
      (node (ref "IC16") (pin "3") (pinfunction "EN_3") (pintype "bidirectional"))
      (node (ref "IC16") (pin "4") (pinfunction "VIN_4") (pintype "bidirectional"))
      (node (ref "IC17") (pin "3") (pinfunction "EN_3") (pintype "bidirectional"))
      (node (ref "IC17") (pin "4") (pinfunction "VIN_4") (pintype "bidirectional"))
      (node (ref "IC18") (pin "2") (pinfunction "VDD_2") (pintype "bidirectional"))
      (node (ref "IC19") (pin "2") (pinfunction "VDD_2") (pintype "bidirectional"))
      (node (ref "IC2") (pin "5") (pinfunction "VCC_5") (pintype "bidirectional"))
      (node (ref "IC20") (pin "2") (pinfunction "VDD_2") (pintype "bidirectional"))
      (node (ref "IC21") (pin "16") (pinfunction "VDD_16") (pintype "bidirectional"))
      (node (ref "IC22") (pin "P$4") (pinfunction "VDD_P$4") (pintype "bidirectional"))
      (node (ref "IC23") (pin "8") (pinfunction "VDD_8") (pintype "bidirectional"))
      (node (ref "IC3") (pin "5") (pinfunction "VCC_5") (pintype "bidirectional"))
      (node (ref "IC4") (pin "5") (pinfunction "VCC_5") (pintype "bidirectional"))
      (node (ref "IC5") (pin "3") (pinfunction "EN_3") (pintype "bidirectional"))
      (node (ref "IC5") (pin "4") (pinfunction "VIN_4") (pintype "bidirectional"))
      (node (ref "IC6") (pin "3") (pinfunction "EN_3") (pintype "bidirectional"))
      (node (ref "IC6") (pin "4") (pinfunction "VIN_4") (pintype "bidirectional"))
      (node (ref "IC7") (pin "3") (pinfunction "EN_3") (pintype "bidirectional"))
      (node (ref "IC7") (pin "4") (pinfunction "VIN_4") (pintype "bidirectional"))
      (node (ref "IC8") (pin "3") (pinfunction "EN_3") (pintype "bidirectional"))
      (node (ref "IC8") (pin "4") (pinfunction "VIN_4") (pintype "bidirectional"))
      (node (ref "R1") (pin "1") (pinfunction "1_1") (pintype "passive"))
      (node (ref "TP5") (pin "TP") (pinfunction "TP_TP") (pintype "input"))
      (node (ref "U$5") (pin "P$4") (pinfunction "VDD_P$4") (pintype "bidirectional"))
    )
    (net (code "69") (name "/VDD2") (class "Default")
      (node (ref "C46") (pin "1") (pinfunction "1_1") (pintype "passive"))
      (node (ref "C5") (pin "1") (pinfunction "1_1") (pintype "passive"))
      (node (ref "C7") (pin "1") (pinfunction "1_1") (pintype "passive"))
      (node (ref "IC10") (pin "3") (pinfunction "EN_3") (pintype "bidirectional"))
      (node (ref "IC10") (pin "4") (pinfunction "VIN_4") (pintype "bidirectional"))
      (node (ref "IC13") (pin "3") (pinfunction "EN_3") (pintype "bidirectional"))
      (node (ref "IC13") (pin "4") (pinfunction "VIN_4") (pintype "bidirectional"))
      (node (ref "IC9") (pin "3") (pinfunction "VO_3") (pintype "passive"))
      (node (ref "TP6") (pin "TP") (pinfunction "TP_TP") (pintype "input"))
    )
    (net (code "70") (name "/VDD_REF_1") (class "Default")
      (node (ref "C26") (pin "1") (pinfunction "1_1") (pintype "passive"))
      (node (ref "IC18") (pin "7") (pinfunction "B_7") (pintype "bidirectional"))
      (node (ref "IC5") (pin "5") (pinfunction "VREF_5") (pintype "bidirectional"))
      (node (ref "R4") (pin "1") (pinfunction "1_1") (pintype "passive"))
    )
    (net (code "71") (name "/VDD_REF_2") (class "Default")
      (node (ref "C27") (pin "1") (pinfunction "1_1") (pintype "passive"))
      (node (ref "IC19") (pin "7") (pinfunction "B_7") (pintype "bidirectional"))
      (node (ref "IC6") (pin "5") (pinfunction "VREF_5") (pintype "bidirectional"))
      (node (ref "R5") (pin "1") (pinfunction "1_1") (pintype "passive"))
    )
    (net (code "72") (name "/VDD_REF_3") (class "Default")
      (node (ref "C35") (pin "1") (pinfunction "1_1") (pintype "passive"))
      (node (ref "IC20") (pin "7") (pinfunction "B_7") (pintype "bidirectional"))
      (node (ref "IC7") (pin "5") (pinfunction "VREF_5") (pintype "bidirectional"))
      (node (ref "R6") (pin "1") (pinfunction "1_1") (pintype "passive"))
    )
    (net (code "73") (name "/VDD_SUPPLY_1") (class "Default")
      (node (ref "C43") (pin "1") (pinfunction "1_1") (pintype "passive"))
      (node (ref "IC11") (pin "1") (pinfunction "VI_1") (pintype "input"))
      (node (ref "JP5") (pin "1") (pinfunction "1_1") (pintype "passive"))
      (node (ref "TP1") (pin "TP") (pinfunction "TP_TP") (pintype "input"))
    )
    (net (code "74") (name "/VDD_SUPPLY_2") (class "Default")
      (node (ref "C45") (pin "1") (pinfunction "1_1") (pintype "passive"))
      (node (ref "IC9") (pin "1") (pinfunction "VI_1") (pintype "input"))
      (node (ref "JP8") (pin "1") (pinfunction "1_1") (pintype "passive"))
      (node (ref "TP3") (pin "TP") (pinfunction "TP_TP") (pintype "input"))
    )
    (net (code "75") (name "/VDD_SUPPLY_IN_1") (class "Default")
      (node (ref "IC12") (pin "8") (pinfunction "V+_8") (pintype "bidirectional"))
      (node (ref "IC14") (pin "8") (pinfunction "V+_8") (pintype "bidirectional"))
      (node (ref "JP3") (pin "3") (pinfunction "3_3") (pintype "passive"))
      (node (ref "JP5") (pin "2") (pinfunction "2_2") (pintype "passive"))
      (node (ref "TP2") (pin "TP") (pinfunction "TP_TP") (pintype "input"))
    )
    (net (code "76") (name "/VDD_SUPPLY_IN_2") (class "Default")
      (node (ref "JP3") (pin "2") (pinfunction "2_2") (pintype "passive"))
      (node (ref "JP8") (pin "2") (pinfunction "2_2") (pintype "passive"))
      (node (ref "TP4") (pin "TP") (pinfunction "TP_TP") (pintype "input"))
    )
    (net (code "77") (name "/VI+_FIL") (class "Default")
      (node (ref "IC1") (pin "22") (pinfunction "VI+_FIL_22") (pintype "input"))
      (node (ref "JP11") (pin "2") (pinfunction "2_2") (pintype "passive"))
    )
    (net (code "78") (name "/VI+_FIL_DAC") (class "Default")
      (node (ref "C54") (pin "1") (pinfunction "1_1") (pintype "passive"))
      (node (ref "IC21") (pin "4") (pinfunction "D1_4") (pintype "bidirectional"))
      (node (ref "JP11") (pin "1") (pinfunction "1_1") (pintype "passive"))
    )
    (net (code "79") (name "/VI-_FIL") (class "Default")
      (node (ref "IC1") (pin "23") (pinfunction "VI-_FIL_23") (pintype "input"))
      (node (ref "JP12") (pin "2") (pinfunction "2_2") (pintype "passive"))
    )
    (net (code "80") (name "/VI-_FIL_DAC") (class "Default")
      (node (ref "C55") (pin "1") (pinfunction "1_1") (pintype "passive"))
      (node (ref "IC21") (pin "7") (pinfunction "D2_7") (pintype "bidirectional"))
      (node (ref "JP12") (pin "1") (pinfunction "1_1") (pintype "passive"))
    )
    (net (code "81") (name "/VICM") (class "Default")
      (node (ref "C32") (pin "1") (pinfunction "1_1") (pintype "passive"))
      (node (ref "IC1") (pin "40") (pinfunction "VICM_40") (pintype "input"))
      (node (ref "IC21") (pin "3") (pinfunction "S1B_3") (pintype "bidirectional"))
      (node (ref "IC21") (pin "6") (pinfunction "S2B_6") (pintype "bidirectional"))
      (node (ref "JP15") (pin "2") (pinfunction "2_2") (pintype "passive"))
      (node (ref "TP12") (pin "TP") (pinfunction "TP_TP") (pintype "input"))
    )
    (net (code "82") (name "/VICM_BUFF") (class "Default")
      (node (ref "IC12") (pin "1") (pinfunction "OUTA_1") (pintype "bidirectional"))
      (node (ref "IC12") (pin "2") (pinfunction "-INA_2") (pintype "bidirectional"))
      (node (ref "JP15") (pin "1") (pinfunction "1_1") (pintype "passive"))
    )
    (net (code "83") (name "/VICM_MUX") (class "Default")
      (node (ref "C47") (pin "1") (pinfunction "1_1") (pintype "passive"))
      (node (ref "IC12") (pin "3") (pinfunction "+INA_3") (pintype "bidirectional"))
      (node (ref "IC3") (pin "4") (pinfunction "B_4") (pintype "bidirectional"))
      (node (ref "JP15") (pin "3") (pinfunction "3_3") (pintype "passive"))
      (node (ref "TP11") (pin "TP") (pinfunction "TP_TP") (pintype "input"))
    )
    (net (code "84") (name "/VIN_CSA") (class "Default")
      (node (ref "IC1") (pin "15") (pinfunction "VIN_CSA_15") (pintype "input"))
      (node (ref "JP1") (pin "3") (pinfunction "3_3") (pintype "passive"))
      (node (ref "JP10") (pin "2") (pinfunction "2_2") (pintype "passive"))
      (node (ref "TP20") (pin "TP") (pinfunction "TP_TP") (pintype "input"))
    )
    (net (code "85") (name "/VIN_CSA_1") (class "Default")
      (node (ref "C36") (pin "1") (pinfunction "1_1") (pintype "passive"))
      (node (ref "C56") (pin "1") (pinfunction "1_1") (pintype "passive"))
      (node (ref "IC21") (pin "9") (pinfunction "D3_9") (pintype "bidirectional"))
      (node (ref "JP9") (pin "1") (pinfunction "1_1") (pintype "passive"))
    )
    (net (code "86") (name "/VL_ADC") (class "Default")
      (node (ref "C14") (pin "1") (pinfunction "1_1") (pintype "passive"))
      (node (ref "C21") (pin "1") (pinfunction "1_1") (pintype "passive"))
      (node (ref "C22") (pin "1") (pinfunction "1_1") (pintype "passive"))
      (node (ref "C29") (pin "1") (pinfunction "1_1") (pintype "passive"))
      (node (ref "C8") (pin "1") (pinfunction "1_1") (pintype "passive"))
      (node (ref "IC16") (pin "5") (pinfunction "VREF_5") (pintype "bidirectional"))
      (node (ref "IC22") (pin "P$7") (pinfunction "VL_P$7") (pintype "bidirectional"))
      (node (ref "TP16") (pin "TP") (pinfunction "TP_TP") (pintype "input"))
      (node (ref "U$5") (pin "P$7") (pinfunction "VL_P$7") (pintype "bidirectional"))
    )
    (net (code "87") (name "/VO+_BP_FIL") (class "Default")
      (node (ref "IC1") (pin "24") (pinfunction "VO+_BP_FIL_24") (pintype "output"))
      (node (ref "JP13") (pin "1") (pinfunction "1_1") (pintype "passive"))
    )
    (net (code "88") (name "/VO+_BP_FIL_TEST") (class "Default")
      (node (ref "JP13") (pin "2") (pinfunction "2_2") (pintype "passive"))
      (node (ref "TP22") (pin "TP") (pinfunction "TP_TP") (pintype "input"))
    )
    (net (code "89") (name "/VO+_CH") (class "Default")
      (node (ref "IC1") (pin "50") (pinfunction "VO+_CH_50") (pintype "input"))
      (node (ref "IC22") (pin "P$12") (pinfunction "AIN+_P$12") (pintype "bidirectional"))
    )
    (net (code "90") (name "/VO+_FIL") (class "Default")
      (node (ref "IC1") (pin "30") (pinfunction "VO+_FIL_30") (pintype "output"))
      (node (ref "U$5") (pin "P$12") (pinfunction "AIN+_P$12") (pintype "bidirectional"))
    )
    (net (code "91") (name "/VO-_BP_FIL") (class "Default")
      (node (ref "IC1") (pin "25") (pinfunction "VO-_BP_FIL_25") (pintype "output"))
      (node (ref "JP14") (pin "1") (pinfunction "1_1") (pintype "passive"))
    )
    (net (code "92") (name "/VO-_BP_FIL_TEST") (class "Default")
      (node (ref "JP14") (pin "2") (pinfunction "2_2") (pintype "passive"))
      (node (ref "TP23") (pin "TP") (pinfunction "TP_TP") (pintype "input"))
    )
    (net (code "93") (name "/VO-_CH") (class "Default")
      (node (ref "IC1") (pin "52") (pinfunction "VO-_CH_52") (pintype "input"))
      (node (ref "IC22") (pin "P$1") (pinfunction "AIN-_P$1") (pintype "bidirectional"))
    )
    (net (code "94") (name "/VO-_FIL") (class "Default")
      (node (ref "IC1") (pin "31") (pinfunction "VO-_FIL_31") (pintype "output"))
      (node (ref "U$5") (pin "P$1") (pinfunction "AIN-_P$1") (pintype "bidirectional"))
    )
    (net (code "95") (name "/VOCM") (class "Default")
      (node (ref "C33") (pin "1") (pinfunction "1_1") (pintype "passive"))
      (node (ref "IC1") (pin "34") (pinfunction "VOCM_AUX_34") (pintype "input"))
      (node (ref "IC1") (pin "36") (pinfunction "VOCM_36") (pintype "input"))
      (node (ref "JP16") (pin "2") (pinfunction "2_2") (pintype "passive"))
      (node (ref "TP14") (pin "TP") (pinfunction "TP_TP") (pintype "input"))
    )
    (net (code "96") (name "/VOCM_1") (class "Default")
      (node (ref "C49") (pin "1") (pinfunction "1_1") (pintype "passive"))
      (node (ref "IC14") (pin "3") (pinfunction "+INA_3") (pintype "bidirectional"))
      (node (ref "IC2") (pin "4") (pinfunction "B_4") (pintype "bidirectional"))
      (node (ref "JP7") (pin "3") (pinfunction "3_3") (pintype "passive"))
      (node (ref "TP30") (pin "TP") (pinfunction "TP_TP") (pintype "input"))
    )
    (net (code "97") (name "/VOCM_BUFF") (class "Default")
      (node (ref "IC12") (pin "6") (pinfunction "-INB_6") (pintype "bidirectional"))
      (node (ref "IC12") (pin "7") (pinfunction "OUTB_7") (pintype "bidirectional"))
      (node (ref "JP16") (pin "1") (pinfunction "1_1") (pintype "passive"))
    )
    (net (code "98") (name "/VOCM_MUX") (class "Default")
      (node (ref "C48") (pin "1") (pinfunction "1_1") (pintype "passive"))
      (node (ref "IC12") (pin "5") (pinfunction "+INB_5") (pintype "bidirectional"))
      (node (ref "IC4") (pin "4") (pinfunction "B_4") (pintype "bidirectional"))
      (node (ref "JP16") (pin "3") (pinfunction "3_3") (pintype "passive"))
      (node (ref "TP13") (pin "TP") (pinfunction "TP_TP") (pintype "input"))
    )
    (net (code "99") (name "/VOUT_CSA") (class "Default")
      (node (ref "IC1") (pin "54") (pinfunction "VOUT_CSA_54") (pintype "output"))
      (node (ref "TP9") (pin "TP") (pinfunction "TP_TP") (pintype "input"))
    )
    (net (code "100") (name "/V_REF_PRECHAR") (class "Default")
      (node (ref "IC1") (pin "7") (pinfunction "V_REF_PRECHAR_7") (pintype "input"))
      (node (ref "JP7") (pin "2") (pinfunction "2_2") (pintype "passive"))
    )
    (net (code "101") (name "/V_REF_PRECHAR_BUFF") (class "Default")
      (node (ref "C34") (pin "1") (pinfunction "1_1") (pintype "passive"))
      (node (ref "IC14") (pin "1") (pinfunction "OUTA_1") (pintype "bidirectional"))
      (node (ref "IC14") (pin "2") (pinfunction "-INA_2") (pintype "bidirectional"))
      (node (ref "JP7") (pin "1") (pinfunction "1_1") (pintype "passive"))
    )
    (net (code "102") (name "/~{CS_ADC1}") (class "Default")
      (node (ref "IC22") (pin "P$9") (pinfunction "CNVST_P$9") (pintype "bidirectional"))
      (node (ref "J1") (pin "A42") (pinfunction "A42_A42") (pintype "bidirectional"))
    )
    (net (code "103") (name "/~{CS_ADC2}") (class "Default")
      (node (ref "J1") (pin "A18") (pinfunction "A18_A18") (pintype "bidirectional"))
      (node (ref "U$5") (pin "P$9") (pinfunction "CNVST_P$9") (pintype "bidirectional"))
    )
    (net (code "104") (name "/~{CS_DAC}") (class "Default")
      (node (ref "IC23") (pin "7") (pinfunction "~{SYNC}_7") (pintype "bidirectional"))
      (node (ref "J1") (pin "A14") (pinfunction "A14_A14") (pintype "bidirectional"))
    )
    (net (code "105") (name "Net-(C36-Pad2)") (class "Default")
      (node (ref "C36") (pin "2") (pinfunction "2_2") (pintype "passive"))
      (node (ref "C37") (pin "1") (pinfunction "1_1") (pintype "passive"))
      (node (ref "JP9") (pin "2") (pinfunction "2_2") (pintype "passive"))
    )
    (net (code "106") (name "Net-(C37-Pad2)") (class "Default")
      (node (ref "C37") (pin "2") (pinfunction "2_2") (pintype "passive"))
      (node (ref "JP10") (pin "1") (pinfunction "1_1") (pintype "passive"))
    )
    (net (code "107") (name "Net-(C38-Pad1)") (class "Default")
      (node (ref "C38") (pin "1") (pinfunction "1_1") (pintype "passive"))
      (node (ref "JP1") (pin "2") (pinfunction "2_2") (pintype "passive"))
    )
    (net (code "108") (name "Net-(C42-Pad1)") (class "Default")
      (node (ref "C42") (pin "1") (pinfunction "1_1") (pintype "passive"))
      (node (ref "J1") (pin "B50") (pinfunction "B50_B50") (pintype "bidirectional"))
      (node (ref "R8") (pin "2") (pinfunction "2_2") (pintype "passive"))
    )
    (net (code "109") (name "Net-(IC18-W)") (class "Default")
      (node (ref "IC18") (pin "1") (pinfunction "W_1") (pintype "bidirectional"))
      (node (ref "IC2") (pin "1") (pinfunction "A0_1") (pintype "bidirectional"))
    )
    (net (code "110") (name "Net-(IC19-W)") (class "Default")
      (node (ref "IC19") (pin "1") (pinfunction "W_1") (pintype "bidirectional"))
      (node (ref "IC3") (pin "1") (pinfunction "A0_1") (pintype "bidirectional"))
    )
    (net (code "111") (name "Net-(IC20-W)") (class "Default")
      (node (ref "IC20") (pin "1") (pinfunction "W_1") (pintype "bidirectional"))
      (node (ref "IC4") (pin "1") (pinfunction "A0_1") (pintype "bidirectional"))
    )
    (net (code "112") (name "Net-(J1-PadA46)") (class "Default")
      (node (ref "J1") (pin "A46") (pinfunction "A46_A46") (pintype "bidirectional"))
      (node (ref "J1") (pin "A48") (pinfunction "A48_A48") (pintype "bidirectional"))
    )
    (net (code "113") (name "Net-(J1-PadB1)") (class "Default")
      (node (ref "J1") (pin "B1") (pinfunction "B1_B1") (pintype "bidirectional"))
      (node (ref "R9") (pin "2") (pinfunction "2_2") (pintype "passive"))
    )
    (net (code "114") (name "unconnected-(IC5-N{slash}C-Pad1)") (class "Default")
      (node (ref "IC5") (pin "1") (pinfunction "N/C_1") (pintype "bidirectional"))
    )
    (net (code "115") (name "unconnected-(IC6-N{slash}C-Pad1)") (class "Default")
      (node (ref "IC6") (pin "1") (pinfunction "N/C_1") (pintype "bidirectional"))
    )
    (net (code "116") (name "unconnected-(IC7-N{slash}C-Pad1)") (class "Default")
      (node (ref "IC7") (pin "1") (pinfunction "N/C_1") (pintype "bidirectional"))
    )
    (net (code "117") (name "unconnected-(IC8-N{slash}C-Pad1)") (class "Default")
      (node (ref "IC8") (pin "1") (pinfunction "N/C_1") (pintype "bidirectional"))
    )
    (net (code "118") (name "unconnected-(IC9-GND-Pad4)") (class "Default")
      (node (ref "IC9") (pin "4") (pinfunction "GND_4") (pintype "passive"))
    )
    (net (code "119") (name "unconnected-(IC10-N{slash}C-Pad1)") (class "Default")
      (node (ref "IC10") (pin "1") (pinfunction "N/C_1") (pintype "bidirectional"))
    )
    (net (code "120") (name "unconnected-(IC11-GND-Pad4)") (class "Default")
      (node (ref "IC11") (pin "4") (pinfunction "GND_4") (pintype "passive"))
    )
    (net (code "121") (name "unconnected-(IC13-N{slash}C-Pad1)") (class "Default")
      (node (ref "IC13") (pin "1") (pinfunction "N/C_1") (pintype "bidirectional"))
    )
    (net (code "122") (name "unconnected-(IC14-+INB-Pad5)") (class "Default")
      (node (ref "IC14") (pin "5") (pinfunction "+INB_5") (pintype "bidirectional"))
    )
    (net (code "123") (name "unconnected-(IC14--INB-Pad6)") (class "Default")
      (node (ref "IC14") (pin "6") (pinfunction "-INB_6") (pintype "bidirectional"))
    )
    (net (code "124") (name "unconnected-(IC14-OUTB-Pad7)") (class "Default")
      (node (ref "IC14") (pin "7") (pinfunction "OUTB_7") (pintype "bidirectional"))
    )
    (net (code "125") (name "unconnected-(IC16-N{slash}C-Pad1)") (class "Default")
      (node (ref "IC16") (pin "1") (pinfunction "N/C_1") (pintype "bidirectional"))
    )
    (net (code "126") (name "unconnected-(IC17-N{slash}C-Pad1)") (class "Default")
      (node (ref "IC17") (pin "1") (pinfunction "N/C_1") (pintype "bidirectional"))
    )
    (net (code "127") (name "unconnected-(J1-PadA1)") (class "Default")
      (node (ref "J1") (pin "A1") (pinfunction "A1_A1") (pintype "bidirectional"))
    )
    (net (code "128") (name "unconnected-(J1-PadA2)") (class "Default")
      (node (ref "J1") (pin "A2") (pinfunction "A2_A2") (pintype "bidirectional"))
    )
    (net (code "129") (name "unconnected-(J1-PadA3)") (class "Default")
      (node (ref "J1") (pin "A3") (pinfunction "A3_A3") (pintype "bidirectional"))
    )
    (net (code "130") (name "unconnected-(J1-PadA4)") (class "Default")
      (node (ref "J1") (pin "A4") (pinfunction "A4_A4") (pintype "bidirectional"))
    )
    (net (code "131") (name "unconnected-(J1-PadA5)") (class "Default")
      (node (ref "J1") (pin "A5") (pinfunction "A5_A5") (pintype "bidirectional"))
    )
    (net (code "132") (name "unconnected-(J1-PadA23)") (class "Default")
      (node (ref "J1") (pin "A23") (pinfunction "A23_A23") (pintype "bidirectional"))
    )
    (net (code "133") (name "unconnected-(J1-PadA29)") (class "Default")
      (node (ref "J1") (pin "A29") (pinfunction "A29_A29") (pintype "bidirectional"))
    )
    (net (code "134") (name "unconnected-(J1-PadA33)") (class "Default")
      (node (ref "J1") (pin "A33") (pinfunction "A33_A33") (pintype "bidirectional"))
    )
    (net (code "135") (name "unconnected-(J1-PadA37)") (class "Default")
      (node (ref "J1") (pin "A37") (pinfunction "A37_A37") (pintype "bidirectional"))
    )
    (net (code "136") (name "unconnected-(J1-PadA41)") (class "Default")
      (node (ref "J1") (pin "A41") (pinfunction "A41_A41") (pintype "bidirectional"))
    )
    (net (code "137") (name "unconnected-(J1-PadA43)") (class "Default")
      (node (ref "J1") (pin "A43") (pinfunction "A43_A43") (pintype "bidirectional"))
    )
    (net (code "138") (name "unconnected-(J1-PadA45)") (class "Default")
      (node (ref "J1") (pin "A45") (pinfunction "A45_A45") (pintype "bidirectional"))
    )
    (net (code "139") (name "unconnected-(J1-PadA47)") (class "Default")
      (node (ref "J1") (pin "A47") (pinfunction "A47_A47") (pintype "bidirectional"))
    )
    (net (code "140") (name "unconnected-(J1-PadA49)") (class "Default")
      (node (ref "J1") (pin "A49") (pinfunction "A49_A49") (pintype "bidirectional"))
    )
    (net (code "141") (name "unconnected-(J1-PadA50)") (class "Default")
      (node (ref "J1") (pin "A50") (pinfunction "A50_A50") (pintype "bidirectional"))
    )
    (net (code "142") (name "unconnected-(J1-PadB3)") (class "Default")
      (node (ref "J1") (pin "B3") (pinfunction "B3_B3") (pintype "bidirectional"))
    )
    (net (code "143") (name "unconnected-(J1-PadB4)") (class "Default")
      (node (ref "J1") (pin "B4") (pinfunction "B4_B4") (pintype "bidirectional"))
    )
    (net (code "144") (name "unconnected-(J1-PadB46)") (class "Default")
      (node (ref "J1") (pin "B46") (pinfunction "B46_B46") (pintype "bidirectional"))
    )
    (net (code "145") (name "unconnected-(J1-PadB48)") (class "Default")
      (node (ref "J1") (pin "B48") (pinfunction "B48_B48") (pintype "bidirectional"))
    )
    (net (code "146") (name "unconnected-(J1-PadB49)") (class "Default")
      (node (ref "J1") (pin "B49") (pinfunction "B49_B49") (pintype "bidirectional"))
    )
  )
)
